# CntrlBoardV3.net
KiCad netlist of a schematic drawn in EAGLE
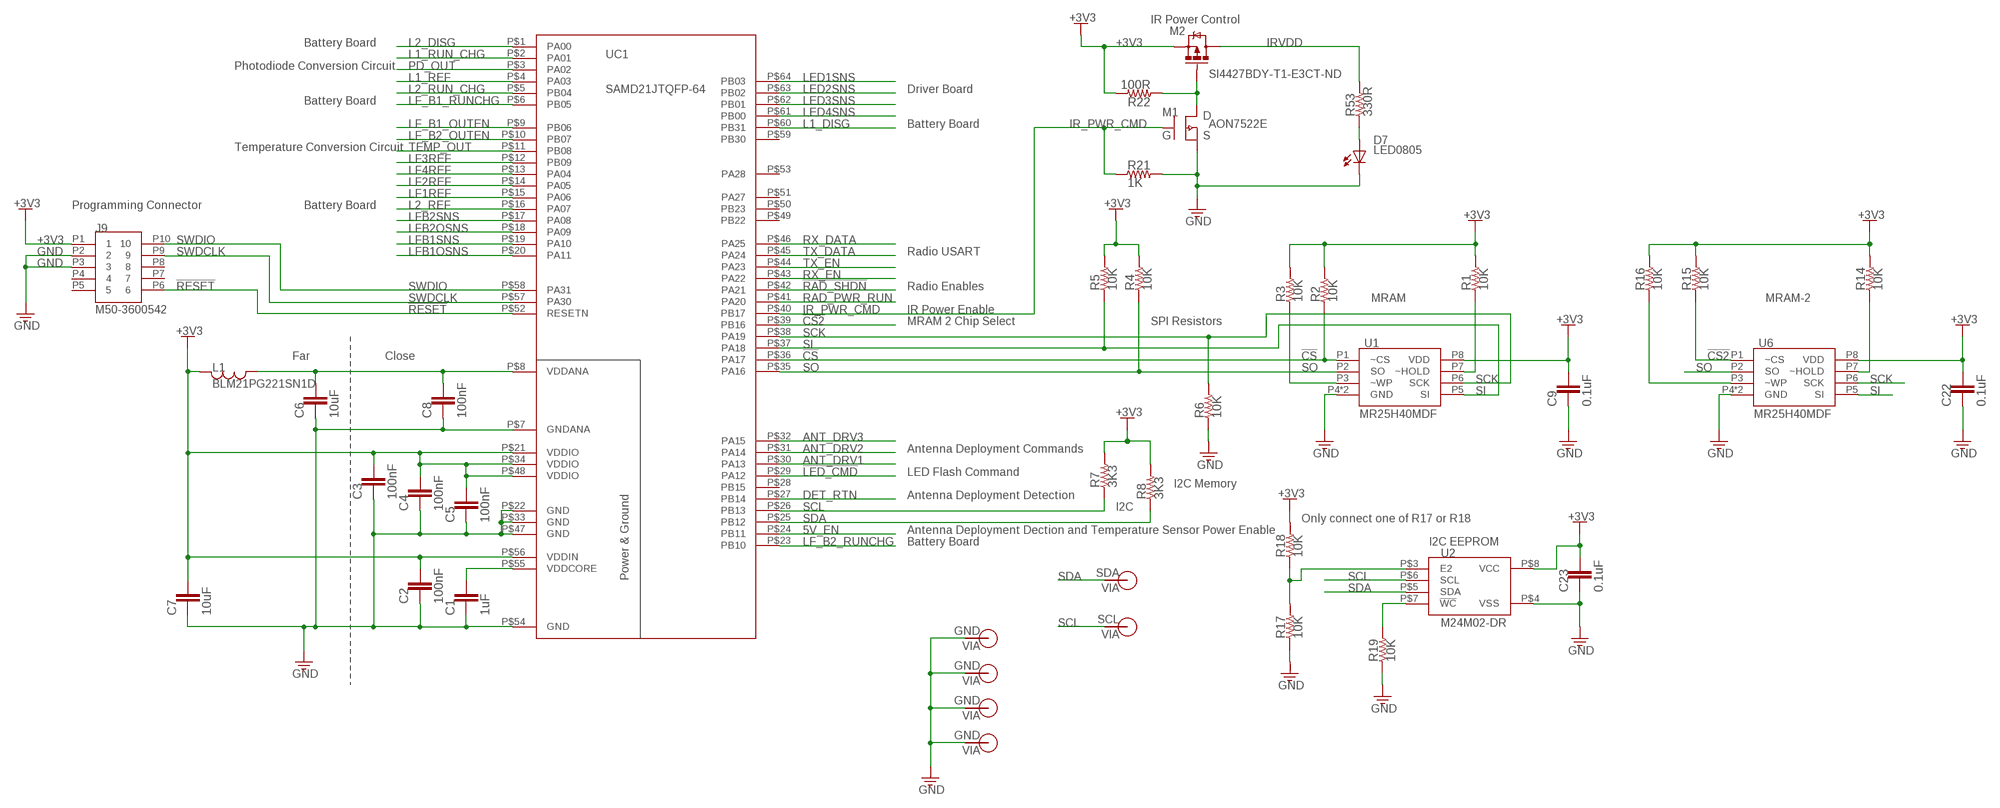
[diagram p0: schematic, sheet 1]
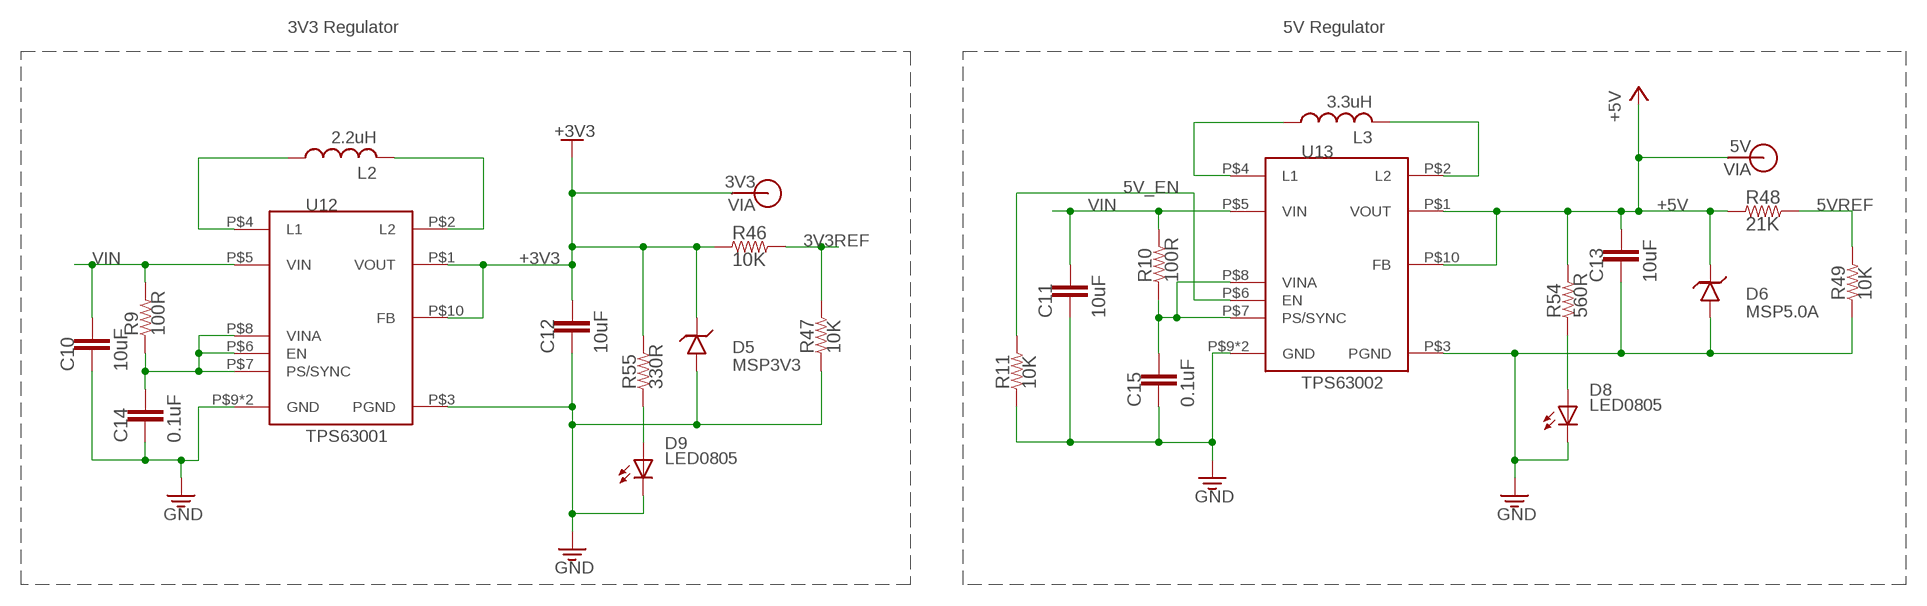
[diagram p1: schematic, sheet 2]
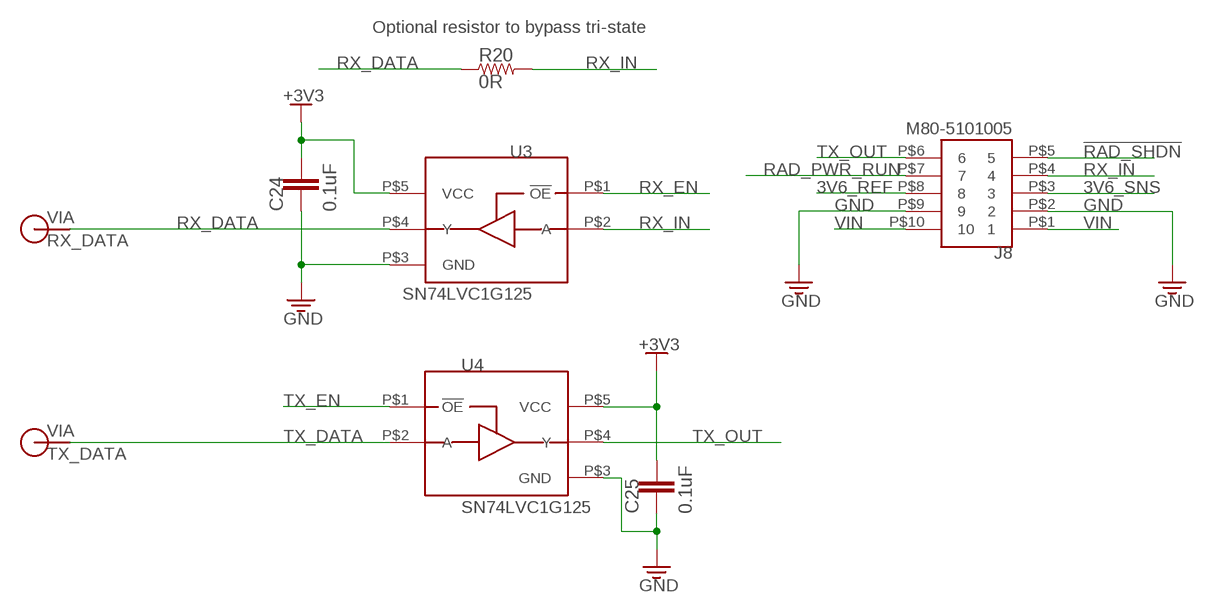
[diagram p2: schematic, sheet 3]
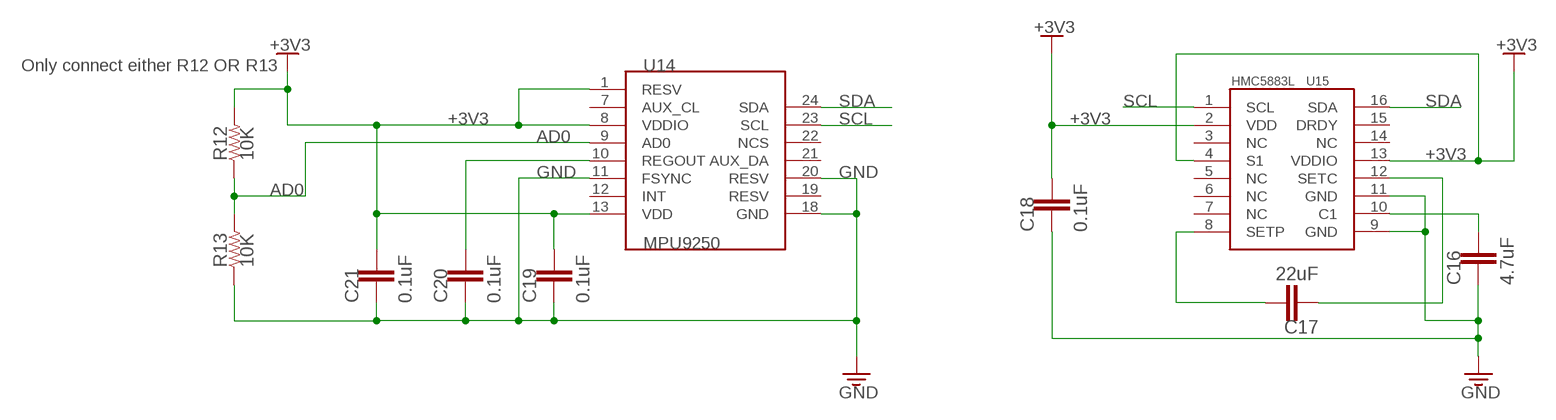
[diagram p3: schematic, sheet 4]
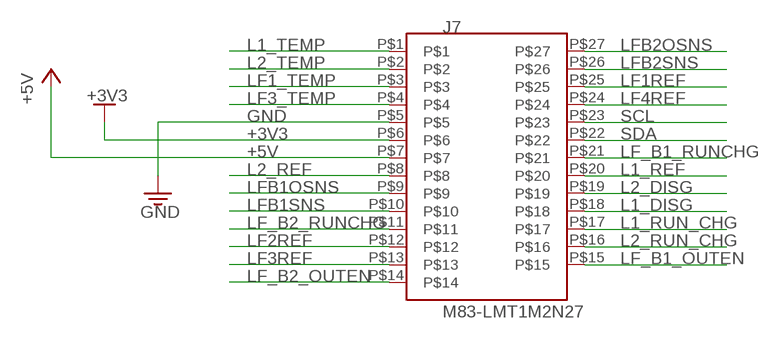
[diagram p4: schematic, sheet 5]
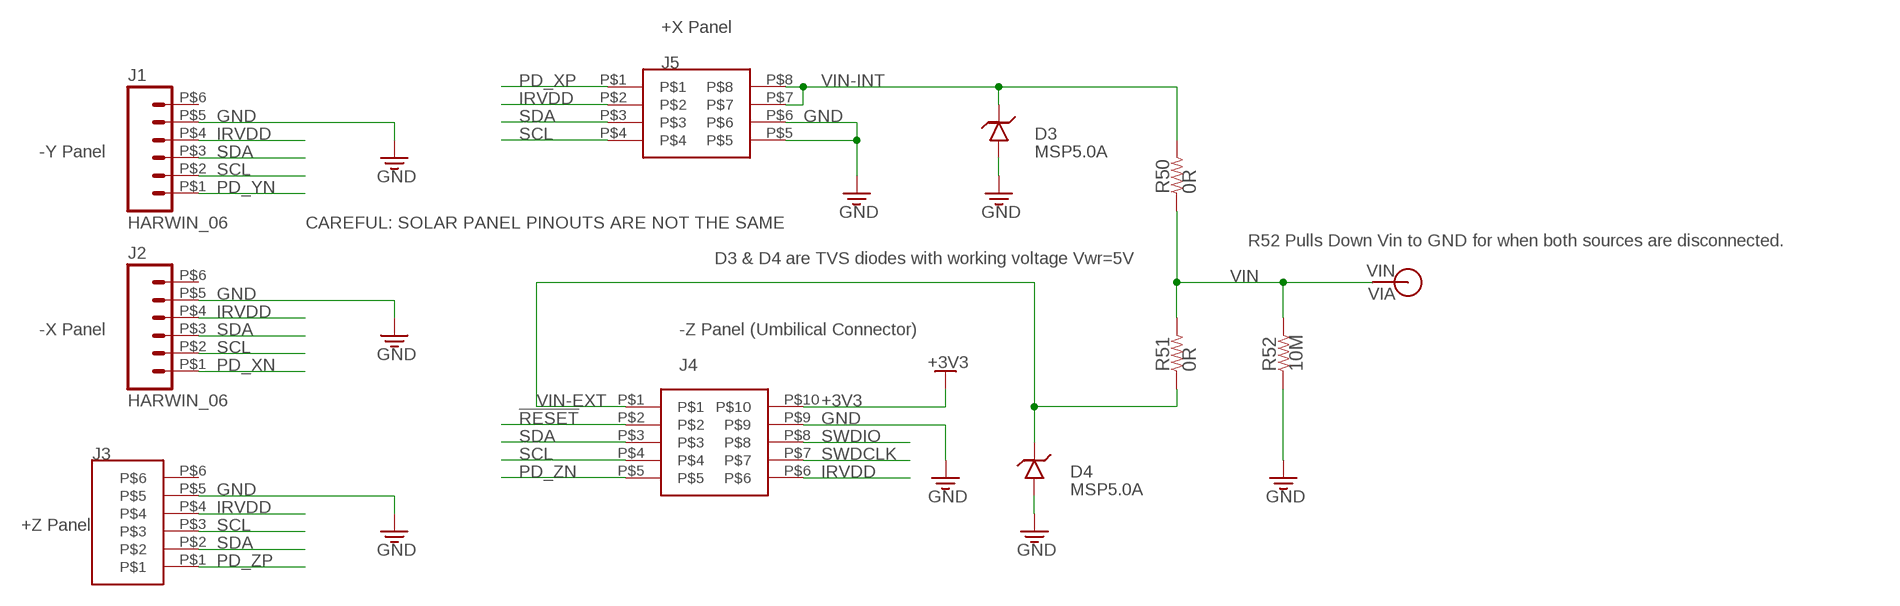
[diagram p5: schematic, sheet 6]
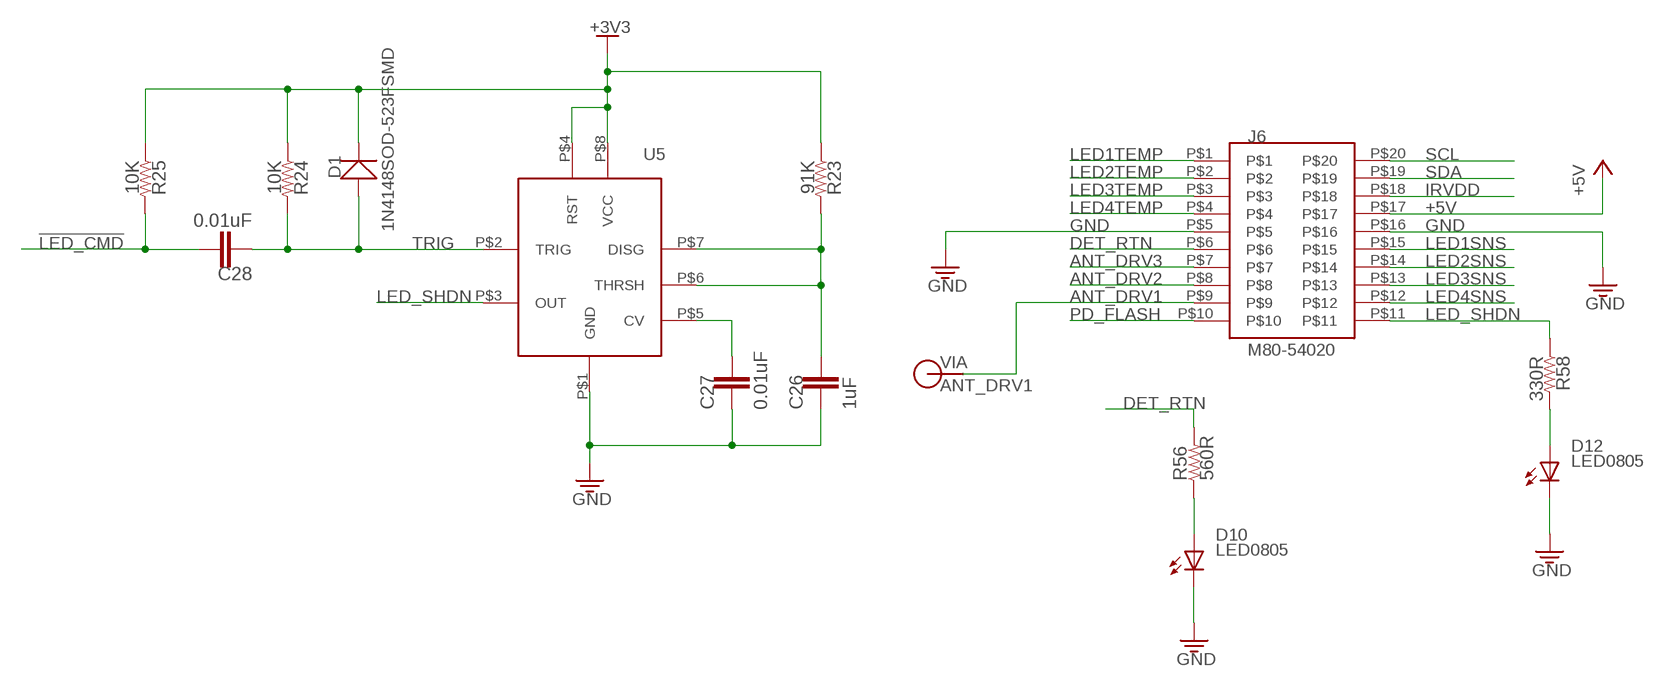
[diagram p6: schematic, sheet 7]
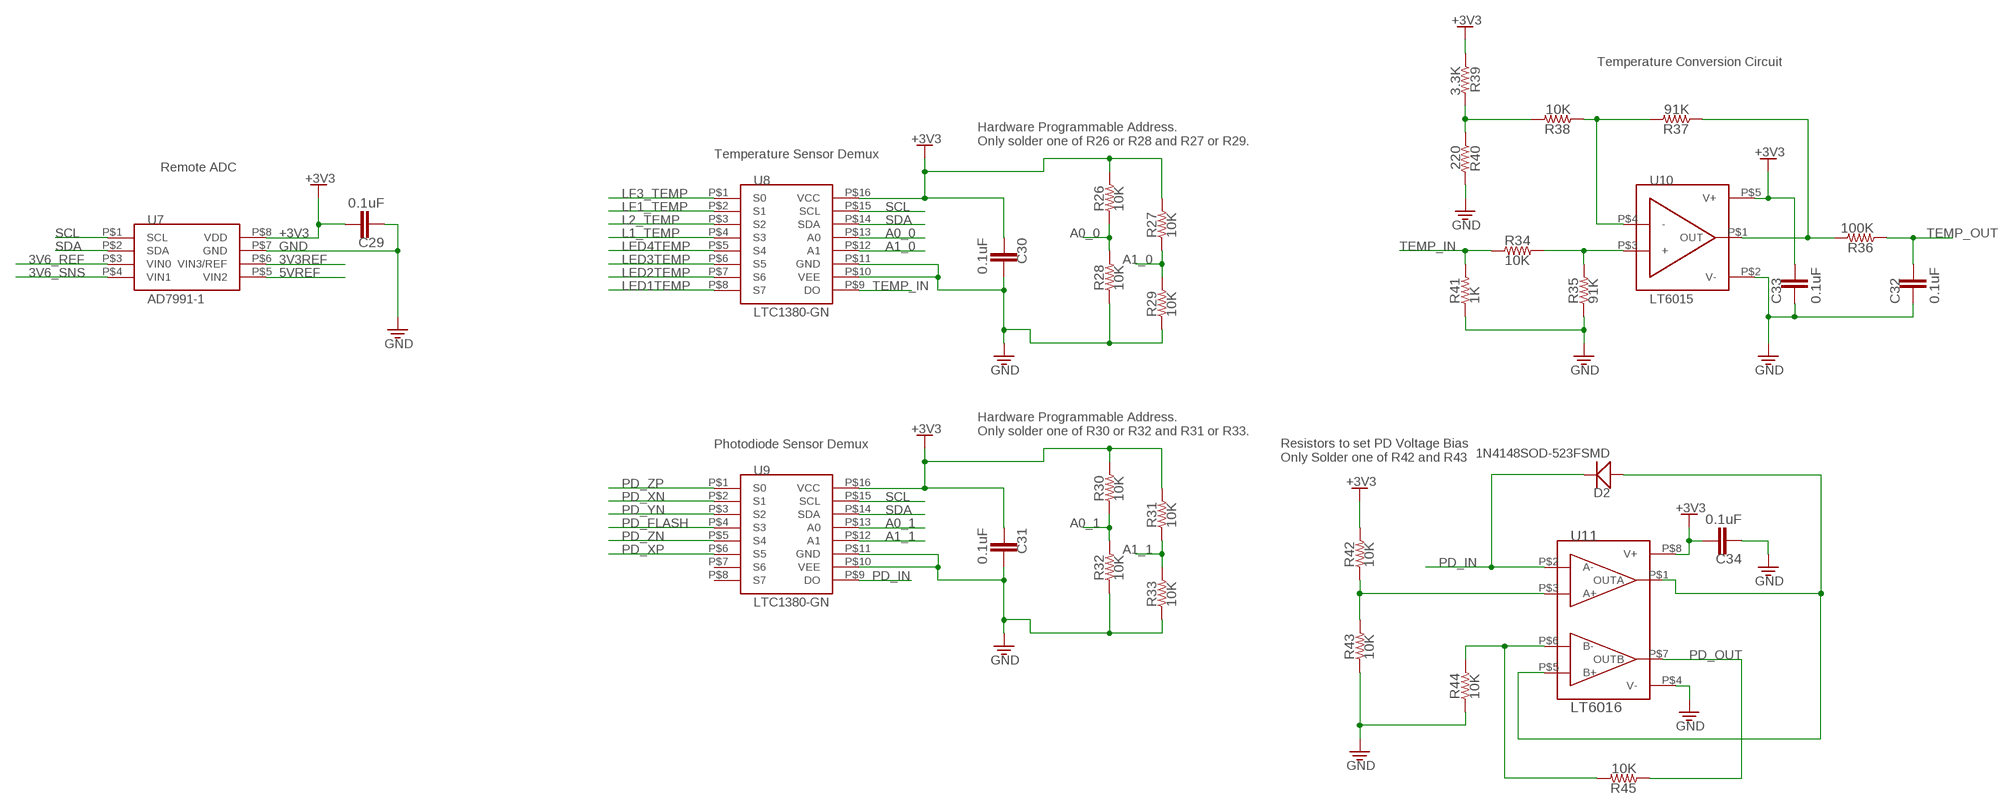
[diagram p7: schematic, sheet 8]

(export (version "E")
  (design (tool "Eeschema 10.0.6"))
  (components
    (comp (ref "C26")
      (value "1uF")
      (footprint "eagle-import:0805")
      (libsource (lib "eagle-import") (part "CAP0805"))
    )
    (comp (ref "C27")
      (value "0.01uF")
      (footprint "eagle-import:0805")
      (libsource (lib "eagle-import") (part "CAP0805"))
    )
    (comp (ref "C28")
      (value "0.01uF")
      (footprint "eagle-import:0805")
      (libsource (lib "eagle-import") (part "CAP0805"))
    )
    (comp (ref "D1")
      (value "1N4148SOD-523FSMD")
      (footprint "eagle-import:SOD-523F")
      (libsource (lib "eagle-import") (part "1N4148SMDSOD-523F"))
    )
    (comp (ref "D10")
      (value "LED0805")
      (footprint "eagle-import:0805-D")
      (libsource (lib "eagle-import") (part "LED0805"))
    )
    (comp (ref "D12")
      (value "LED0805")
      (footprint "eagle-import:0805-D")
      (libsource (lib "eagle-import") (part "LED0805"))
    )
    (comp (ref "J6")
      (value "M80-54020")
      (footprint "eagle-import:M80-54020")
      (libsource (lib "eagle-import") (part "M80-54020"))
    )
    (comp (ref "R23")
      (value "91K")
      (footprint "eagle-import:0805")
      (libsource (lib "eagle-import") (part "RES0805"))
    )
    (comp (ref "R24")
      (value "10K")
      (footprint "eagle-import:0805")
      (libsource (lib "eagle-import") (part "RES0805"))
    )
    (comp (ref "R25")
      (value "10K")
      (footprint "eagle-import:0805")
      (libsource (lib "eagle-import") (part "RES0805"))
    )
    (comp (ref "R56")
      (value "560R")
      (footprint "eagle-import:0805")
      (libsource (lib "eagle-import") (part "RES0805"))
    )
    (comp (ref "R58")
      (value "330R")
      (footprint "eagle-import:0805")
      (libsource (lib "eagle-import") (part "RES0805"))
    )
    (comp (ref "U5")
      (value "TLC555")
      (footprint "eagle-import:SO-8")
      (libsource (lib "eagle-import") (part "TLC555"))
    )
    (comp (ref "V6")
      (value "ANT_DRV1")
      (footprint "eagle-import:VIA-60MIL-SQ")
      (libsource (lib "eagle-import") (part "VIA60MIL-SQ"))
    )
    (comp (ref "C16")
      (value "4.7uF")
      (footprint "eagle-import:0805")
      (libsource (lib "eagle-import") (part "CAP0805"))
    )
    (comp (ref "C17")
      (value "22uF")
      (footprint "eagle-import:0805")
      (libsource (lib "eagle-import") (part "CAP0805"))
    )
    (comp (ref "C18")
      (value "0.1uF")
      (footprint "eagle-import:0805")
      (libsource (lib "eagle-import") (part "CAP0805"))
    )
    (comp (ref "C19")
      (value "0.1uF")
      (footprint "eagle-import:0805")
      (libsource (lib "eagle-import") (part "CAP0805"))
    )
    (comp (ref "C20")
      (value "0.1uF")
      (footprint "eagle-import:0805")
      (libsource (lib "eagle-import") (part "CAP0805"))
    )
    (comp (ref "C21")
      (value "0.1uF")
      (footprint "eagle-import:0805")
      (libsource (lib "eagle-import") (part "CAP0805"))
    )
    (comp (ref "R12")
      (value "10K")
      (footprint "eagle-import:0805")
      (libsource (lib "eagle-import") (part "RES0805"))
    )
    (comp (ref "R13")
      (value "10K")
      (footprint "eagle-import:0805")
      (libsource (lib "eagle-import") (part "RES0805"))
    )
    (comp (ref "U14")
      (value "MPU9250")
      (footprint "eagle-import:QFN-24-3X3")
      (libsource (lib "eagle-import") (part "MPU9250"))
    )
    (comp (ref "U15")
      (value "HMC5883L")
      (footprint "eagle-import:HMC5883L")
      (libsource (lib "eagle-import") (part "HMC5883L"))
    )
    (comp (ref "C10")
      (value "10uF")
      (footprint "eagle-import:0805")
      (libsource (lib "eagle-import") (part "CAP0805"))
    )
    (comp (ref "C11")
      (value "10uF")
      (footprint "eagle-import:0805")
      (libsource (lib "eagle-import") (part "CAP0805"))
    )
    (comp (ref "C12")
      (value "10uF")
      (footprint "eagle-import:0805")
      (libsource (lib "eagle-import") (part "CAP0805"))
    )
    (comp (ref "C13")
      (value "10uF")
      (footprint "eagle-import:0805")
      (libsource (lib "eagle-import") (part "CAP0805"))
    )
    (comp (ref "C14")
      (value "0.1uF")
      (footprint "eagle-import:0805")
      (libsource (lib "eagle-import") (part "CAP0805"))
    )
    (comp (ref "C15")
      (value "0.1uF")
      (footprint "eagle-import:0805")
      (libsource (lib "eagle-import") (part "CAP0805"))
    )
    (comp (ref "D5")
      (value "MSP3V3")
      (footprint "eagle-import:MICROSMP")
      (libsource (lib "eagle-import") (part "TVSMSP"))
    )
    (comp (ref "D6")
      (value "MSP5.0A")
      (footprint "eagle-import:MICROSMP")
      (libsource (lib "eagle-import") (part "TVSMSP"))
    )
    (comp (ref "D8")
      (value "LED0805")
      (footprint "eagle-import:0805-D")
      (libsource (lib "eagle-import") (part "LED0805"))
    )
    (comp (ref "D9")
      (value "LED0805")
      (footprint "eagle-import:0805-D")
      (libsource (lib "eagle-import") (part "LED0805"))
    )
    (comp (ref "L2")
      (value "2.2uH")
      (footprint "eagle-import:L3225M")
      (libsource (lib "eagle-import") (part "L-USL3225M"))
    )
    (comp (ref "L3")
      (value "3.3uH")
      (footprint "eagle-import:L3225M")
      (libsource (lib "eagle-import") (part "L-USL3225M"))
    )
    (comp (ref "R9")
      (value "100R")
      (footprint "eagle-import:0805")
      (libsource (lib "eagle-import") (part "RES0805"))
    )
    (comp (ref "R10")
      (value "100R")
      (footprint "eagle-import:0805")
      (libsource (lib "eagle-import") (part "RES0805"))
    )
    (comp (ref "R11")
      (value "10K")
      (footprint "eagle-import:0805")
      (libsource (lib "eagle-import") (part "RES0805"))
    )
    (comp (ref "R46")
      (value "10K")
      (footprint "eagle-import:0805")
      (libsource (lib "eagle-import") (part "RES0805"))
    )
    (comp (ref "R47")
      (value "10K")
      (footprint "eagle-import:0805")
      (libsource (lib "eagle-import") (part "RES0805"))
    )
    (comp (ref "R48")
      (value "21K")
      (footprint "eagle-import:0805")
      (libsource (lib "eagle-import") (part "RES0805"))
    )
    (comp (ref "R49")
      (value "10K")
      (footprint "eagle-import:0805")
      (libsource (lib "eagle-import") (part "RES0805"))
    )
    (comp (ref "R54")
      (value "560R")
      (footprint "eagle-import:0805")
      (libsource (lib "eagle-import") (part "RES0805"))
    )
    (comp (ref "R55")
      (value "330R")
      (footprint "eagle-import:0805")
      (libsource (lib "eagle-import") (part "RES0805"))
    )
    (comp (ref "U12")
      (value "TPS63001")
      (footprint "eagle-import:QFN10_POWERPAD")
      (libsource (lib "eagle-import") (part "TPS6300X"))
    )
    (comp (ref "U13")
      (value "TPS63002")
      (footprint "eagle-import:QFN10_POWERPAD")
      (libsource (lib "eagle-import") (part "TPS6300X"))
    )
    (comp (ref "V13")
      (value "3V3")
      (footprint "eagle-import:VIA-60MIL-SQ")
      (libsource (lib "eagle-import") (part "VIA60MIL-SQ"))
    )
    (comp (ref "V14")
      (value "5V")
      (footprint "eagle-import:VIA-60MIL-SQ")
      (libsource (lib "eagle-import") (part "VIA60MIL-SQ"))
    )
    (comp (ref "C29")
      (value "0.1uF")
      (footprint "eagle-import:0805")
      (libsource (lib "eagle-import") (part "CAP0805"))
    )
    (comp (ref "C30")
      (value "0.1uF")
      (footprint "eagle-import:0805")
      (libsource (lib "eagle-import") (part "CAP0805"))
    )
    (comp (ref "C31")
      (value "0.1uF")
      (footprint "eagle-import:0805")
      (libsource (lib "eagle-import") (part "CAP0805"))
    )
    (comp (ref "C32")
      (value "0.1uF")
      (footprint "eagle-import:0805")
      (libsource (lib "eagle-import") (part "CAP0805"))
    )
    (comp (ref "C33")
      (value "0.1uF")
      (footprint "eagle-import:0805")
      (libsource (lib "eagle-import") (part "CAP0805"))
    )
    (comp (ref "C34")
      (value "0.1uF")
      (footprint "eagle-import:0805")
      (libsource (lib "eagle-import") (part "CAP0805"))
    )
    (comp (ref "D2")
      (value "1N4148SOD-523FSMD")
      (footprint "eagle-import:SOD-523F")
      (libsource (lib "eagle-import") (part "1N4148SMDSOD-523F"))
    )
    (comp (ref "R26")
      (value "10K")
      (footprint "eagle-import:0805")
      (libsource (lib "eagle-import") (part "RES0805"))
    )
    (comp (ref "R27")
      (value "10K")
      (footprint "eagle-import:0805")
      (libsource (lib "eagle-import") (part "RES0805"))
    )
    (comp (ref "R28")
      (value "10K")
      (footprint "eagle-import:0805")
      (libsource (lib "eagle-import") (part "RES0805"))
    )
    (comp (ref "R29")
      (value "10K")
      (footprint "eagle-import:0805")
      (libsource (lib "eagle-import") (part "RES0805"))
    )
    (comp (ref "R30")
      (value "10K")
      (footprint "eagle-import:0805")
      (libsource (lib "eagle-import") (part "RES0805"))
    )
    (comp (ref "R31")
      (value "10K")
      (footprint "eagle-import:0805")
      (libsource (lib "eagle-import") (part "RES0805"))
    )
    (comp (ref "R32")
      (value "10K")
      (footprint "eagle-import:0805")
      (libsource (lib "eagle-import") (part "RES0805"))
    )
    (comp (ref "R33")
      (value "10K")
      (footprint "eagle-import:0805")
      (libsource (lib "eagle-import") (part "RES0805"))
    )
    (comp (ref "R34")
      (value "10K")
      (footprint "eagle-import:0805")
      (libsource (lib "eagle-import") (part "RES0805"))
    )
    (comp (ref "R35")
      (value "91K")
      (footprint "eagle-import:0805")
      (libsource (lib "eagle-import") (part "RES0805"))
    )
    (comp (ref "R36")
      (value "100K")
      (footprint "eagle-import:0805")
      (libsource (lib "eagle-import") (part "RES0805"))
    )
    (comp (ref "R37")
      (value "91K")
      (footprint "eagle-import:0805")
      (libsource (lib "eagle-import") (part "RES0805"))
    )
    (comp (ref "R38")
      (value "10K")
      (footprint "eagle-import:0805")
      (libsource (lib "eagle-import") (part "RES0805"))
    )
    (comp (ref "R39")
      (value "3.3K")
      (footprint "eagle-import:0805")
      (libsource (lib "eagle-import") (part "RES0805"))
    )
    (comp (ref "R40")
      (value "220")
      (footprint "eagle-import:0805")
      (libsource (lib "eagle-import") (part "RES0805"))
    )
    (comp (ref "R41")
      (value "1K")
      (footprint "eagle-import:0805")
      (libsource (lib "eagle-import") (part "RES0805"))
    )
    (comp (ref "R42")
      (value "10K")
      (footprint "eagle-import:0805")
      (libsource (lib "eagle-import") (part "RES0805"))
    )
    (comp (ref "R43")
      (value "10K")
      (footprint "eagle-import:0805")
      (libsource (lib "eagle-import") (part "RES0805"))
    )
    (comp (ref "R44")
      (value "10K")
      (footprint "eagle-import:0805")
      (libsource (lib "eagle-import") (part "RES0805"))
    )
    (comp (ref "R45")
      (value "10K")
      (footprint "eagle-import:0805")
      (libsource (lib "eagle-import") (part "RES0805"))
    )
    (comp (ref "U7")
      (value "AD7991-1")
      (footprint "eagle-import:SOT-23-8")
      (libsource (lib "eagle-import") (part "AD7991-1"))
    )
    (comp (ref "U8")
      (value "LTC1380-GN")
      (footprint "eagle-import:SSOP-16-NARROW")
      (libsource (lib "eagle-import") (part "LTC1380-GN"))
    )
    (comp (ref "U9")
      (value "LTC1380-GN")
      (footprint "eagle-import:SSOP-16-NARROW")
      (libsource (lib "eagle-import") (part "LTC1380-GN"))
    )
    (comp (ref "U10")
      (value "LT6015")
      (footprint "eagle-import:TSOT23-5")
      (libsource (lib "eagle-import") (part "LT6015"))
    )
    (comp (ref "U11")
      (value "LT6016")
      (footprint "eagle-import:MSOP-8")
      (libsource (lib "eagle-import") (part "LT6016"))
    )
    (comp (ref "C1")
      (value "1uF")
      (footprint "eagle-import:0805")
      (libsource (lib "eagle-import") (part "CAP0805"))
    )
    (comp (ref "C2")
      (value "100nF")
      (footprint "eagle-import:0805")
      (libsource (lib "eagle-import") (part "CAP0805"))
    )
    (comp (ref "C3")
      (value "100nF")
      (footprint "eagle-import:0805")
      (libsource (lib "eagle-import") (part "CAP0805"))
    )
    (comp (ref "C4")
      (value "100nF")
      (footprint "eagle-import:0805")
      (libsource (lib "eagle-import") (part "CAP0805"))
    )
    (comp (ref "C5")
      (value "100nF")
      (footprint "eagle-import:0805")
      (libsource (lib "eagle-import") (part "CAP0805"))
    )
    (comp (ref "C6")
      (value "10uF")
      (footprint "eagle-import:0805")
      (libsource (lib "eagle-import") (part "CAP0805"))
    )
    (comp (ref "C7")
      (value "10uF")
      (footprint "eagle-import:0805")
      (libsource (lib "eagle-import") (part "CAP0805"))
    )
    (comp (ref "C8")
      (value "100nF")
      (footprint "eagle-import:0805")
      (libsource (lib "eagle-import") (part "CAP0805"))
    )
    (comp (ref "C9")
      (value "0.1uF")
      (footprint "eagle-import:0805")
      (libsource (lib "eagle-import") (part "CAP0805"))
    )
    (comp (ref "C22")
      (value "0.1uF")
      (footprint "eagle-import:0805")
      (libsource (lib "eagle-import") (part "CAP0805"))
    )
    (comp (ref "C23")
      (value "0.1uF")
      (footprint "eagle-import:0805")
      (libsource (lib "eagle-import") (part "CAP0805"))
    )
    (comp (ref "D7")
      (value "LED0805")
      (footprint "eagle-import:0805-D")
      (libsource (lib "eagle-import") (part "LED0805"))
    )
    (comp (ref "J9")
      (value "M50-3600542")
      (footprint "eagle-import:10PINMALE")
      (libsource (lib "eagle-import") (part "10PINMALE"))
    )
    (comp (ref "L1")
      (value "BLM21PG221SN1D")
      (footprint "eagle-import:0805")
      (libsource (lib "eagle-import") (part "FERRITE"))
    )
    (comp (ref "M1")
      (value "AON7522E")
      (footprint "eagle-import:DFN-3X3-8")
      (libsource (lib "eagle-import") (part "AON7522E"))
    )
    (comp (ref "M2")
      (value "SI4427BDY-T1-E3CT-ND")
      (footprint "eagle-import:SO08")
      (libsource (lib "eagle-import") (part "POWERPMOS"))
    )
    (comp (ref "R1")
      (value "10K")
      (footprint "eagle-import:0805")
      (libsource (lib "eagle-import") (part "RES0805"))
    )
    (comp (ref "R2")
      (value "10K")
      (footprint "eagle-import:0805")
      (libsource (lib "eagle-import") (part "RES0805"))
    )
    (comp (ref "R3")
      (value "10K")
      (footprint "eagle-import:0805")
      (libsource (lib "eagle-import") (part "RES0805"))
    )
    (comp (ref "R4")
      (value "10K")
      (footprint "eagle-import:0805")
      (libsource (lib "eagle-import") (part "RES0805"))
    )
    (comp (ref "R5")
      (value "10K")
      (footprint "eagle-import:0805")
      (libsource (lib "eagle-import") (part "RES0805"))
    )
    (comp (ref "R6")
      (value "10K")
      (footprint "eagle-import:0805")
      (libsource (lib "eagle-import") (part "RES0805"))
    )
    (comp (ref "R7")
      (value "3K3")
      (footprint "eagle-import:0805")
      (libsource (lib "eagle-import") (part "RES0805"))
    )
    (comp (ref "R8")
      (value "3K3")
      (footprint "eagle-import:0805")
      (libsource (lib "eagle-import") (part "RES0805"))
    )
    (comp (ref "R14")
      (value "10K")
      (footprint "eagle-import:0805")
      (libsource (lib "eagle-import") (part "RES0805"))
    )
    (comp (ref "R15")
      (value "10K")
      (footprint "eagle-import:0805")
      (libsource (lib "eagle-import") (part "RES0805"))
    )
    (comp (ref "R16")
      (value "10K")
      (footprint "eagle-import:0805")
      (libsource (lib "eagle-import") (part "RES0805"))
    )
    (comp (ref "R17")
      (value "10K")
      (footprint "eagle-import:0805")
      (libsource (lib "eagle-import") (part "RES0805"))
    )
    (comp (ref "R18")
      (value "10K")
      (footprint "eagle-import:0805")
      (libsource (lib "eagle-import") (part "RES0805"))
    )
    (comp (ref "R19")
      (value "10K")
      (footprint "eagle-import:0805")
      (libsource (lib "eagle-import") (part "RES0805"))
    )
    (comp (ref "R21")
      (value "1K")
      (footprint "eagle-import:0805")
      (libsource (lib "eagle-import") (part "RES0805"))
    )
    (comp (ref "R22")
      (value "100R")
      (footprint "eagle-import:0805")
      (libsource (lib "eagle-import") (part "RES0805"))
    )
    (comp (ref "R53")
      (value "330R")
      (footprint "eagle-import:0805")
      (libsource (lib "eagle-import") (part "RES0805"))
    )
    (comp (ref "U1")
      (value "MR25H40MDF")
      (footprint "eagle-import:8PXMO-229")
      (libsource (lib "eagle-import") (part "MR2XHXX"))
    )
    (comp (ref "U2")
      (value "M24M02-DR")
      (footprint "eagle-import:SO-8")
      (libsource (lib "eagle-import") (part "M24M02-DR"))
    )
    (comp (ref "U6")
      (value "MR25H40MDF")
      (footprint "eagle-import:8PXMO-229")
      (libsource (lib "eagle-import") (part "MR2XHXX"))
    )
    (comp (ref "UC1")
      (value "SAMD21JTQFP-64")
      (footprint "eagle-import:TQFP-64")
      (libsource (lib "eagle-import") (part "SAMD21JTQFP-64"))
    )
    (comp (ref "V4")
      (value "SDA")
      (footprint "eagle-import:VIA-60MIL-SQ")
      (libsource (lib "eagle-import") (part "VIA60MIL-SQ"))
    )
    (comp (ref "V5")
      (value "SCL")
      (footprint "eagle-import:VIA-60MIL-SQ")
      (libsource (lib "eagle-import") (part "VIA60MIL-SQ"))
    )
    (comp (ref "V9")
      (value "GND")
      (footprint "eagle-import:VIA-60MIL-SQ")
      (libsource (lib "eagle-import") (part "VIA60MIL-SQ"))
    )
    (comp (ref "V10")
      (value "GND")
      (footprint "eagle-import:VIA-60MIL-SQ")
      (libsource (lib "eagle-import") (part "VIA60MIL-SQ"))
    )
    (comp (ref "V11")
      (value "GND")
      (footprint "eagle-import:VIA-60MIL-SQ")
      (libsource (lib "eagle-import") (part "VIA60MIL-SQ"))
    )
    (comp (ref "V12")
      (value "GND")
      (footprint "eagle-import:VIA-60MIL-SQ")
      (libsource (lib "eagle-import") (part "VIA60MIL-SQ"))
    )
    (comp (ref "D3")
      (value "MSP5.0A")
      (footprint "eagle-import:MICROSMP")
      (libsource (lib "eagle-import") (part "TVSMSP"))
    )
    (comp (ref "D4")
      (value "MSP5.0A")
      (footprint "eagle-import:MICROSMP")
      (libsource (lib "eagle-import") (part "TVSMSP"))
    )
    (comp (ref "J1")
      (value "HARWIN_06")
      (footprint "eagle-import:HARWIN_DATAMATE_6")
      (libsource (lib "eagle-import") (part "HARWIN_06"))
    )
    (comp (ref "J2")
      (value "HARWIN_06")
      (footprint "eagle-import:HARWIN_DATAMATE_6")
      (libsource (lib "eagle-import") (part "HARWIN_06"))
    )
    (comp (ref "J3")
      (value "M80-54006")
      (footprint "eagle-import:M80-54006")
      (libsource (lib "eagle-import") (part "M80-54006"))
    )
    (comp (ref "J4")
      (value "M80-54010")
      (footprint "eagle-import:M80-54010")
      (libsource (lib "eagle-import") (part "M80-54010"))
    )
    (comp (ref "J5")
      (value "M80-54008")
      (footprint "eagle-import:M80-54008")
      (libsource (lib "eagle-import") (part "M80-54008"))
    )
    (comp (ref "R50")
      (value "0R")
      (footprint "eagle-import:1210")
      (libsource (lib "eagle-import") (part "RES1210"))
    )
    (comp (ref "R51")
      (value "0R")
      (footprint "eagle-import:1210")
      (libsource (lib "eagle-import") (part "RES1210"))
    )
    (comp (ref "R52")
      (value "10M")
      (footprint "eagle-import:0805")
      (libsource (lib "eagle-import") (part "RES0805"))
    )
    (comp (ref "V3")
      (value "VIN")
      (footprint "eagle-import:VIA-60MIL-SQ")
      (libsource (lib "eagle-import") (part "VIA60MIL-SQ"))
    )
    (comp (ref "C24")
      (value "0.1uF")
      (footprint "eagle-import:0805")
      (libsource (lib "eagle-import") (part "CAP0805"))
    )
    (comp (ref "C25")
      (value "0.1uF")
      (footprint "eagle-import:0805")
      (libsource (lib "eagle-import") (part "CAP0805"))
    )
    (comp (ref "J8")
      (value "M80-5101005")
      (footprint "eagle-import:M80-510")
      (libsource (lib "eagle-import") (part "M80-5101005"))
    )
    (comp (ref "R20")
      (value "0R")
      (footprint "eagle-import:0805")
      (libsource (lib "eagle-import") (part "RES0805"))
    )
    (comp (ref "U3")
      (value "SN74LVC1G125")
      (footprint "eagle-import:TSOT23-5")
      (libsource (lib "eagle-import") (part "SN74LVC1G125"))
    )
    (comp (ref "U4")
      (value "SN74LVC1G125")
      (footprint "eagle-import:TSOT23-5")
      (libsource (lib "eagle-import") (part "SN74LVC1G125"))
    )
    (comp (ref "V1")
      (value "RX_DATA")
      (footprint "eagle-import:VIA-60MIL-SQ")
      (libsource (lib "eagle-import") (part "VIA60MIL-SQ"))
    )
    (comp (ref "V2")
      (value "TX_DATA")
      (footprint "eagle-import:VIA-60MIL-SQ")
      (libsource (lib "eagle-import") (part "VIA60MIL-SQ"))
    )
    (comp (ref "J7")
      (value "M83-LMT1M2N27")
      (footprint "eagle-import:M83-LMT1M2N27")
      (libsource (lib "eagle-import") (part "M83-LMT1M2N27"))
    )
  )
  (nets
    (net (code "1") (name "+3V3") (class "Default")
      (node (ref "C12") (pin "1") (pinfunction "P$1_1") (pintype "passive"))
      (node (ref "C18") (pin "1") (pinfunction "P$1_1") (pintype "passive"))
      (node (ref "C19") (pin "1") (pinfunction "P$1_1") (pintype "passive"))
      (node (ref "C2") (pin "1") (pinfunction "P$1_1") (pintype "passive"))
      (node (ref "C21") (pin "1") (pinfunction "P$1_1") (pintype "passive"))
      (node (ref "C22") (pin "1") (pinfunction "P$1_1") (pintype "passive"))
      (node (ref "C23") (pin "1") (pinfunction "P$1_1") (pintype "passive"))
      (node (ref "C24") (pin "1") (pinfunction "P$1_1") (pintype "passive"))
      (node (ref "C25") (pin "1") (pinfunction "P$1_1") (pintype "passive"))
      (node (ref "C29") (pin "1") (pinfunction "P$1_1") (pintype "passive"))
      (node (ref "C3") (pin "1") (pinfunction "P$1_1") (pintype "passive"))
      (node (ref "C30") (pin "2") (pinfunction "P$2_2") (pintype "passive"))
      (node (ref "C31") (pin "2") (pinfunction "P$2_2") (pintype "passive"))
      (node (ref "C33") (pin "1") (pinfunction "P$1_1") (pintype "passive"))
      (node (ref "C34") (pin "1") (pinfunction "P$1_1") (pintype "passive"))
      (node (ref "C4") (pin "1") (pinfunction "P$1_1") (pintype "passive"))
      (node (ref "C5") (pin "1") (pinfunction "P$1_1") (pintype "passive"))
      (node (ref "C7") (pin "1") (pinfunction "P$1_1") (pintype "passive"))
      (node (ref "C9") (pin "1") (pinfunction "P$1_1") (pintype "passive"))
      (node (ref "D1") (pin "C") (pinfunction "C_C") (pintype "bidirectional"))
      (node (ref "D5") (pin "C") (pinfunction "C_C") (pintype "bidirectional"))
      (node (ref "J4") (pin "P$10") (pinfunction "P$10_P$10") (pintype "bidirectional"))
      (node (ref "J7") (pin "P$6") (pinfunction "P$6_P$6") (pintype "bidirectional"))
      (node (ref "J9") (pin "P1") (pinfunction "1_P1") (pintype "bidirectional"))
      (node (ref "L1") (pin "1") (pinfunction "P$1_1") (pintype "passive"))
      (node (ref "M2") (pin "1") (pinfunction "S_1") (pintype "passive"))
      (node (ref "M2") (pin "2") (pinfunction "S_2") (pintype "passive"))
      (node (ref "M2") (pin "3") (pinfunction "S_3") (pintype "passive"))
      (node (ref "R1") (pin "2") (pinfunction "2_2") (pintype "passive"))
      (node (ref "R12") (pin "2") (pinfunction "2_2") (pintype "passive"))
      (node (ref "R14") (pin "2") (pinfunction "2_2") (pintype "passive"))
      (node (ref "R15") (pin "2") (pinfunction "2_2") (pintype "passive"))
      (node (ref "R16") (pin "2") (pinfunction "2_2") (pintype "passive"))
      (node (ref "R18") (pin "2") (pinfunction "2_2") (pintype "passive"))
      (node (ref "R2") (pin "2") (pinfunction "2_2") (pintype "passive"))
      (node (ref "R22") (pin "2") (pinfunction "2_2") (pintype "passive"))
      (node (ref "R23") (pin "1") (pinfunction "1_1") (pintype "passive"))
      (node (ref "R24") (pin "1") (pinfunction "1_1") (pintype "passive"))
      (node (ref "R25") (pin "1") (pinfunction "1_1") (pintype "passive"))
      (node (ref "R26") (pin "2") (pinfunction "2_2") (pintype "passive"))
      (node (ref "R27") (pin "2") (pinfunction "2_2") (pintype "passive"))
      (node (ref "R3") (pin "2") (pinfunction "2_2") (pintype "passive"))
      (node (ref "R30") (pin "2") (pinfunction "2_2") (pintype "passive"))
      (node (ref "R31") (pin "2") (pinfunction "2_2") (pintype "passive"))
      (node (ref "R39") (pin "1") (pinfunction "1_1") (pintype "passive"))
      (node (ref "R4") (pin "2") (pinfunction "2_2") (pintype "passive"))
      (node (ref "R42") (pin "2") (pinfunction "2_2") (pintype "passive"))
      (node (ref "R46") (pin "1") (pinfunction "1_1") (pintype "passive"))
      (node (ref "R5") (pin "2") (pinfunction "2_2") (pintype "passive"))
      (node (ref "R55") (pin "2") (pinfunction "2_2") (pintype "passive"))
      (node (ref "R7") (pin "2") (pinfunction "2_2") (pintype "passive"))
      (node (ref "R8") (pin "2") (pinfunction "2_2") (pintype "passive"))
      (node (ref "U1") (pin "P8") (pinfunction "VDD_P8") (pintype "bidirectional"))
      (node (ref "U10") (pin "P$5") (pinfunction "V+_P$5") (pintype "bidirectional"))
      (node (ref "U11") (pin "P$8") (pinfunction "V+_P$8") (pintype "bidirectional"))
      (node (ref "U12") (pin "P$1") (pinfunction "VOUT_P$1") (pintype "output"))
      (node (ref "U12") (pin "P$10") (pinfunction "FB_P$10") (pintype "input"))
      (node (ref "U14") (pin "1") (pinfunction "RESV_1") (pintype "bidirectional"))
      (node (ref "U14") (pin "13") (pinfunction "VDD_13") (pintype "bidirectional"))
      (node (ref "U14") (pin "8") (pinfunction "VDDIO_8") (pintype "bidirectional"))
      (node (ref "U15") (pin "13") (pinfunction "VDDIO_13") (pintype "bidirectional"))
      (node (ref "U15") (pin "2") (pinfunction "VDD_2") (pintype "bidirectional"))
      (node (ref "U15") (pin "4") (pinfunction "S1_4") (pintype "bidirectional"))
      (node (ref "U2") (pin "P$8") (pinfunction "VCC_P$8") (pintype "bidirectional"))
      (node (ref "U3") (pin "P$5") (pinfunction "VCC_P$5") (pintype "bidirectional"))
      (node (ref "U4") (pin "P$5") (pinfunction "VCC_P$5") (pintype "bidirectional"))
      (node (ref "U5") (pin "P$4") (pinfunction "RST_P$4") (pintype "bidirectional"))
      (node (ref "U5") (pin "P$8") (pinfunction "VCC_P$8") (pintype "bidirectional"))
      (node (ref "U6") (pin "P8") (pinfunction "VDD_P8") (pintype "bidirectional"))
      (node (ref "U7") (pin "P$8") (pinfunction "VDD_P$8") (pintype "bidirectional"))
      (node (ref "U8") (pin "P$16") (pinfunction "VCC_P$16") (pintype "bidirectional"))
      (node (ref "U9") (pin "P$16") (pinfunction "VCC_P$16") (pintype "bidirectional"))
      (node (ref "UC1") (pin "P$21") (pinfunction "VDDIO_P$21") (pintype "power_in"))
      (node (ref "UC1") (pin "P$34") (pinfunction "VDDIO_P$34") (pintype "power_in"))
      (node (ref "UC1") (pin "P$48") (pinfunction "VDDIO_P$48") (pintype "power_in"))
      (node (ref "UC1") (pin "P$56") (pinfunction "VDDIN_P$56") (pintype "power_in"))
      (node (ref "V13") (pin "P$1") (pinfunction "P$1_P$1") (pintype "bidirectional"))
    )
    (net (code "2") (name "+5V") (class "Default")
      (node (ref "C13") (pin "1") (pinfunction "P$1_1") (pintype "passive"))
      (node (ref "D6") (pin "C") (pinfunction "C_C") (pintype "bidirectional"))
      (node (ref "J6") (pin "P$17") (pinfunction "P$17_P$17") (pintype "bidirectional"))
      (node (ref "J7") (pin "P$7") (pinfunction "P$7_P$7") (pintype "bidirectional"))
      (node (ref "R48") (pin "1") (pinfunction "1_1") (pintype "passive"))
      (node (ref "R54") (pin "2") (pinfunction "2_2") (pintype "passive"))
      (node (ref "U13") (pin "P$1") (pinfunction "VOUT_P$1") (pintype "output"))
      (node (ref "U13") (pin "P$10") (pinfunction "FB_P$10") (pintype "input"))
      (node (ref "V14") (pin "P$1") (pinfunction "P$1_P$1") (pintype "bidirectional"))
    )
    (net (code "3") (name "3V3REF") (class "Default")
      (node (ref "R46") (pin "2") (pinfunction "2_2") (pintype "passive"))
      (node (ref "R47") (pin "2") (pinfunction "2_2") (pintype "passive"))
      (node (ref "U7") (pin "P$6") (pinfunction "VIN3/REF_P$6") (pintype "bidirectional"))
    )
    (net (code "4") (name "3V6_REF") (class "Default")
      (node (ref "J8") (pin "P$8") (pinfunction "8_P$8") (pintype "bidirectional"))
      (node (ref "U7") (pin "P$3") (pinfunction "VIN0_P$3") (pintype "bidirectional"))
    )
    (net (code "5") (name "3V6_SNS") (class "Default")
      (node (ref "J8") (pin "P$3") (pinfunction "3_P$3") (pintype "bidirectional"))
      (node (ref "U7") (pin "P$4") (pinfunction "VIN1_P$4") (pintype "bidirectional"))
    )
    (net (code "6") (name "5VREF") (class "Default")
      (node (ref "R48") (pin "2") (pinfunction "2_2") (pintype "passive"))
      (node (ref "R49") (pin "2") (pinfunction "2_2") (pintype "passive"))
      (node (ref "U7") (pin "P$5") (pinfunction "VIN2_P$5") (pintype "bidirectional"))
    )
    (net (code "7") (name "5V_EN") (class "Default")
      (node (ref "R11") (pin "2") (pinfunction "2_2") (pintype "passive"))
      (node (ref "U13") (pin "P$6") (pinfunction "EN_P$6") (pintype "input"))
      (node (ref "UC1") (pin "P$24") (pinfunction "PB11_P$24") (pintype "bidirectional"))
    )
    (net (code "8") (name "A0_0") (class "Default")
      (node (ref "R26") (pin "1") (pinfunction "1_1") (pintype "passive"))
      (node (ref "R28") (pin "2") (pinfunction "2_2") (pintype "passive"))
      (node (ref "U8") (pin "P$13") (pinfunction "A0_P$13") (pintype "bidirectional"))
    )
    (net (code "9") (name "A0_1") (class "Default")
      (node (ref "R30") (pin "1") (pinfunction "1_1") (pintype "passive"))
      (node (ref "R32") (pin "2") (pinfunction "2_2") (pintype "passive"))
      (node (ref "U9") (pin "P$13") (pinfunction "A0_P$13") (pintype "bidirectional"))
    )
    (net (code "10") (name "A1_0") (class "Default")
      (node (ref "R27") (pin "1") (pinfunction "1_1") (pintype "passive"))
      (node (ref "R29") (pin "2") (pinfunction "2_2") (pintype "passive"))
      (node (ref "U8") (pin "P$12") (pinfunction "A1_P$12") (pintype "bidirectional"))
    )
    (net (code "11") (name "A1_1") (class "Default")
      (node (ref "R31") (pin "1") (pinfunction "1_1") (pintype "passive"))
      (node (ref "R33") (pin "2") (pinfunction "2_2") (pintype "passive"))
      (node (ref "U9") (pin "P$12") (pinfunction "A1_P$12") (pintype "bidirectional"))
    )
    (net (code "12") (name "AD0") (class "Default")
      (node (ref "R12") (pin "1") (pinfunction "1_1") (pintype "passive"))
      (node (ref "R13") (pin "2") (pinfunction "2_2") (pintype "passive"))
      (node (ref "U14") (pin "9") (pinfunction "AD0_9") (pintype "bidirectional"))
    )
    (net (code "13") (name "ANT_DRV1") (class "Default")
      (node (ref "J6") (pin "P$9") (pinfunction "P$9_P$9") (pintype "bidirectional"))
      (node (ref "UC1") (pin "P$30") (pinfunction "PA13_P$30") (pintype "bidirectional"))
      (node (ref "V6") (pin "P$1") (pinfunction "P$1_P$1") (pintype "bidirectional"))
    )
    (net (code "14") (name "ANT_DRV2") (class "Default")
      (node (ref "J6") (pin "P$8") (pinfunction "P$8_P$8") (pintype "bidirectional"))
      (node (ref "UC1") (pin "P$31") (pinfunction "PA14_P$31") (pintype "bidirectional"))
    )
    (net (code "15") (name "ANT_DRV3") (class "Default")
      (node (ref "J6") (pin "P$7") (pinfunction "P$7_P$7") (pintype "bidirectional"))
      (node (ref "UC1") (pin "P$32") (pinfunction "PA15_P$32") (pintype "bidirectional"))
    )
    (net (code "16") (name "DET_RTN") (class "Default")
      (node (ref "J6") (pin "P$6") (pinfunction "P$6_P$6") (pintype "bidirectional"))
      (node (ref "R56") (pin "2") (pinfunction "2_2") (pintype "passive"))
      (node (ref "UC1") (pin "P$27") (pinfunction "PB14_P$27") (pintype "bidirectional"))
    )
    (net (code "17") (name "GND") (class "Default")
      (node (ref "C1") (pin "2") (pinfunction "P$2_2") (pintype "passive"))
      (node (ref "C10") (pin "2") (pinfunction "P$2_2") (pintype "passive"))
      (node (ref "C11") (pin "2") (pinfunction "P$2_2") (pintype "passive"))
      (node (ref "C12") (pin "2") (pinfunction "P$2_2") (pintype "passive"))
      (node (ref "C13") (pin "2") (pinfunction "P$2_2") (pintype "passive"))
      (node (ref "C14") (pin "2") (pinfunction "P$2_2") (pintype "passive"))
      (node (ref "C15") (pin "2") (pinfunction "P$2_2") (pintype "passive"))
      (node (ref "C16") (pin "2") (pinfunction "P$2_2") (pintype "passive"))
      (node (ref "C18") (pin "2") (pinfunction "P$2_2") (pintype "passive"))
      (node (ref "C19") (pin "2") (pinfunction "P$2_2") (pintype "passive"))
      (node (ref "C2") (pin "2") (pinfunction "P$2_2") (pintype "passive"))
      (node (ref "C20") (pin "2") (pinfunction "P$2_2") (pintype "passive"))
      (node (ref "C21") (pin "2") (pinfunction "P$2_2") (pintype "passive"))
      (node (ref "C22") (pin "2") (pinfunction "P$2_2") (pintype "passive"))
      (node (ref "C23") (pin "2") (pinfunction "P$2_2") (pintype "passive"))
      (node (ref "C24") (pin "2") (pinfunction "P$2_2") (pintype "passive"))
      (node (ref "C25") (pin "2") (pinfunction "P$2_2") (pintype "passive"))
      (node (ref "C26") (pin "2") (pinfunction "P$2_2") (pintype "passive"))
      (node (ref "C27") (pin "2") (pinfunction "P$2_2") (pintype "passive"))
      (node (ref "C29") (pin "2") (pinfunction "P$2_2") (pintype "passive"))
      (node (ref "C3") (pin "2") (pinfunction "P$2_2") (pintype "passive"))
      (node (ref "C30") (pin "1") (pinfunction "P$1_1") (pintype "passive"))
      (node (ref "C31") (pin "1") (pinfunction "P$1_1") (pintype "passive"))
      (node (ref "C32") (pin "2") (pinfunction "P$2_2") (pintype "passive"))
      (node (ref "C33") (pin "2") (pinfunction "P$2_2") (pintype "passive"))
      (node (ref "C34") (pin "2") (pinfunction "P$2_2") (pintype "passive"))
      (node (ref "C4") (pin "2") (pinfunction "P$2_2") (pintype "passive"))
      (node (ref "C5") (pin "2") (pinfunction "P$2_2") (pintype "passive"))
      (node (ref "C6") (pin "2") (pinfunction "P$2_2") (pintype "passive"))
      (node (ref "C7") (pin "2") (pinfunction "P$2_2") (pintype "passive"))
      (node (ref "C8") (pin "2") (pinfunction "P$2_2") (pintype "passive"))
      (node (ref "C9") (pin "2") (pinfunction "P$2_2") (pintype "passive"))
      (node (ref "D10") (pin "C") (pinfunction "C_C") (pintype "passive"))
      (node (ref "D12") (pin "C") (pinfunction "C_C") (pintype "passive"))
      (node (ref "D3") (pin "A") (pinfunction "A_A") (pintype "bidirectional"))
      (node (ref "D4") (pin "A") (pinfunction "A_A") (pintype "bidirectional"))
      (node (ref "D5") (pin "A") (pinfunction "A_A") (pintype "bidirectional"))
      (node (ref "D6") (pin "A") (pinfunction "A_A") (pintype "bidirectional"))
      (node (ref "D7") (pin "C") (pinfunction "C_C") (pintype "passive"))
      (node (ref "D8") (pin "C") (pinfunction "C_C") (pintype "passive"))
      (node (ref "D9") (pin "C") (pinfunction "C_C") (pintype "passive"))
      (node (ref "J1") (pin "P$5") (pinfunction "5_P$5") (pintype "passive"))
      (node (ref "J2") (pin "P$5") (pinfunction "5_P$5") (pintype "passive"))
      (node (ref "J3") (pin "P$5") (pinfunction "P$5_P$5") (pintype "bidirectional"))
      (node (ref "J4") (pin "P$9") (pinfunction "P$9_P$9") (pintype "bidirectional"))
      (node (ref "J5") (pin "P$5") (pinfunction "P$5_P$5") (pintype "bidirectional"))
      (node (ref "J5") (pin "P$6") (pinfunction "P$6_P$6") (pintype "bidirectional"))
      (node (ref "J6") (pin "P$16") (pinfunction "P$16_P$16") (pintype "bidirectional"))
      (node (ref "J6") (pin "P$5") (pinfunction "P$5_P$5") (pintype "bidirectional"))
      (node (ref "J7") (pin "P$5") (pinfunction "P$5_P$5") (pintype "bidirectional"))
      (node (ref "J8") (pin "P$2") (pinfunction "2_P$2") (pintype "bidirectional"))
      (node (ref "J8") (pin "P$9") (pinfunction "9_P$9") (pintype "bidirectional"))
      (node (ref "J9") (pin "P2") (pinfunction "2_P2") (pintype "bidirectional"))
      (node (ref "J9") (pin "P3") (pinfunction "3_P3") (pintype "bidirectional"))
      (node (ref "M1") (pin "P$1") (pinfunction "S_P$1") (pintype "bidirectional"))
      (node (ref "M1") (pin "P$2") (pinfunction "S_P$2") (pintype "bidirectional"))
      (node (ref "M1") (pin "P$3") (pinfunction "S_P$3") (pintype "bidirectional"))
      (node (ref "R11") (pin "1") (pinfunction "1_1") (pintype "passive"))
      (node (ref "R13") (pin "1") (pinfunction "1_1") (pintype "passive"))
      (node (ref "R17") (pin "1") (pinfunction "1_1") (pintype "passive"))
      (node (ref "R19") (pin "1") (pinfunction "1_1") (pintype "passive"))
      (node (ref "R21") (pin "2") (pinfunction "2_2") (pintype "passive"))
      (node (ref "R28") (pin "1") (pinfunction "1_1") (pintype "passive"))
      (node (ref "R29") (pin "1") (pinfunction "1_1") (pintype "passive"))
      (node (ref "R32") (pin "1") (pinfunction "1_1") (pintype "passive"))
      (node (ref "R33") (pin "1") (pinfunction "1_1") (pintype "passive"))
      (node (ref "R35") (pin "1") (pinfunction "1_1") (pintype "passive"))
      (node (ref "R40") (pin "2") (pinfunction "2_2") (pintype "passive"))
      (node (ref "R41") (pin "1") (pinfunction "1_1") (pintype "passive"))
      (node (ref "R43") (pin "1") (pinfunction "1_1") (pintype "passive"))
      (node (ref "R44") (pin "1") (pinfunction "1_1") (pintype "passive"))
      (node (ref "R47") (pin "1") (pinfunction "1_1") (pintype "passive"))
      (node (ref "R49") (pin "1") (pinfunction "1_1") (pintype "passive"))
      (node (ref "R52") (pin "1") (pinfunction "1_1") (pintype "passive"))
      (node (ref "R6") (pin "1") (pinfunction "1_1") (pintype "passive"))
      (node (ref "U1") (pin "P4") (pinfunction "GND_P4") (pintype "bidirectional"))
      (node (ref "U1") (pin "P9") (pinfunction "GND_P9") (pintype "bidirectional"))
      (node (ref "U10") (pin "P$2") (pinfunction "V-_P$2") (pintype "bidirectional"))
      (node (ref "U11") (pin "P$4") (pinfunction "V-_P$4") (pintype "bidirectional"))
      (node (ref "U12") (pin "P$3") (pinfunction "PGND_P$3") (pintype "input"))
      (node (ref "U12") (pin "P$9") (pinfunction "GND_P$9") (pintype "input"))
      (node (ref "U12") (pin "PAD") (pinfunction "GND_PAD") (pintype "input"))
      (node (ref "U13") (pin "P$3") (pinfunction "PGND_P$3") (pintype "input"))
      (node (ref "U13") (pin "P$9") (pinfunction "GND_P$9") (pintype "input"))
      (node (ref "U13") (pin "PAD") (pinfunction "GND_PAD") (pintype "input"))
      (node (ref "U14") (pin "11") (pinfunction "FSYNC_11") (pintype "bidirectional"))
      (node (ref "U14") (pin "18") (pinfunction "GND_18") (pintype "bidirectional"))
      (node (ref "U14") (pin "20") (pinfunction "RESV_20") (pintype "bidirectional"))
      (node (ref "U15") (pin "11") (pinfunction "GND_11") (pintype "bidirectional"))
      (node (ref "U15") (pin "9") (pinfunction "GND_9") (pintype "bidirectional"))
      (node (ref "U2") (pin "P$4") (pinfunction "VSS_P$4") (pintype "bidirectional"))
      (node (ref "U3") (pin "P$3") (pinfunction "GND_P$3") (pintype "bidirectional"))
      (node (ref "U4") (pin "P$3") (pinfunction "GND_P$3") (pintype "bidirectional"))
      (node (ref "U5") (pin "P$1") (pinfunction "GND_P$1") (pintype "bidirectional"))
      (node (ref "U6") (pin "P4") (pinfunction "GND_P4") (pintype "bidirectional"))
      (node (ref "U6") (pin "P9") (pinfunction "GND_P9") (pintype "bidirectional"))
      (node (ref "U7") (pin "P$7") (pinfunction "GND_P$7") (pintype "bidirectional"))
      (node (ref "U8") (pin "P$10") (pinfunction "VEE_P$10") (pintype "bidirectional"))
      (node (ref "U8") (pin "P$11") (pinfunction "GND_P$11") (pintype "bidirectional"))
      (node (ref "U9") (pin "P$10") (pinfunction "VEE_P$10") (pintype "bidirectional"))
      (node (ref "U9") (pin "P$11") (pinfunction "GND_P$11") (pintype "bidirectional"))
      (node (ref "UC1") (pin "P$22") (pinfunction "GND_P$22") (pintype "power_in"))
      (node (ref "UC1") (pin "P$33") (pinfunction "GND_P$33") (pintype "power_in"))
      (node (ref "UC1") (pin "P$47") (pinfunction "GND_P$47") (pintype "power_in"))
      (node (ref "UC1") (pin "P$54") (pinfunction "GND_P$54") (pintype "power_in"))
      (node (ref "UC1") (pin "P$7") (pinfunction "GNDANA_P$7") (pintype "power_in"))
      (node (ref "V10") (pin "P$1") (pinfunction "P$1_P$1") (pintype "bidirectional"))
      (node (ref "V11") (pin "P$1") (pinfunction "P$1_P$1") (pintype "bidirectional"))
      (node (ref "V12") (pin "P$1") (pinfunction "P$1_P$1") (pintype "bidirectional"))
      (node (ref "V9") (pin "P$1") (pinfunction "P$1_P$1") (pintype "bidirectional"))
    )
    (net (code "18") (name "IRVDD") (class "Default")
      (node (ref "J1") (pin "P$4") (pinfunction "4_P$4") (pintype "passive"))
      (node (ref "J2") (pin "P$4") (pinfunction "4_P$4") (pintype "passive"))
      (node (ref "J3") (pin "P$4") (pinfunction "P$4_P$4") (pintype "bidirectional"))
      (node (ref "J4") (pin "P$6") (pinfunction "P$6_P$6") (pintype "bidirectional"))
      (node (ref "J5") (pin "P$2") (pinfunction "P$2_P$2") (pintype "bidirectional"))
      (node (ref "J6") (pin "P$18") (pinfunction "P$18_P$18") (pintype "bidirectional"))
      (node (ref "M2") (pin "5") (pinfunction "D_5") (pintype "passive"))
      (node (ref "M2") (pin "6") (pinfunction "D_6") (pintype "passive"))
      (node (ref "M2") (pin "7") (pinfunction "D_7") (pintype "passive"))
      (node (ref "M2") (pin "8") (pinfunction "D_8") (pintype "passive"))
      (node (ref "R53") (pin "2") (pinfunction "2_2") (pintype "passive"))
    )
    (net (code "19") (name "IR_PWR_CMD") (class "Default")
      (node (ref "M1") (pin "P$4") (pinfunction "G_P$4") (pintype "bidirectional"))
      (node (ref "R21") (pin "1") (pinfunction "1_1") (pintype "passive"))
      (node (ref "UC1") (pin "P$40") (pinfunction "PB17_P$40") (pintype "bidirectional"))
    )
    (net (code "20") (name "L1_DISG") (class "Default")
      (node (ref "J7") (pin "P$18") (pinfunction "P$18_P$18") (pintype "bidirectional"))
      (node (ref "UC1") (pin "P$60") (pinfunction "PB31_P$60") (pintype "bidirectional"))
    )
    (net (code "21") (name "L1_REF") (class "Default")
      (node (ref "J7") (pin "P$20") (pinfunction "P$20_P$20") (pintype "bidirectional"))
      (node (ref "UC1") (pin "P$4") (pinfunction "PA03_P$4") (pintype "bidirectional"))
    )
    (net (code "22") (name "L1_RUN_CHG") (class "Default")
      (node (ref "J7") (pin "P$17") (pinfunction "P$17_P$17") (pintype "bidirectional"))
      (node (ref "UC1") (pin "P$2") (pinfunction "PA01_P$2") (pintype "bidirectional"))
    )
    (net (code "23") (name "L1_TEMP") (class "Default")
      (node (ref "J7") (pin "P$1") (pinfunction "P$1_P$1") (pintype "bidirectional"))
      (node (ref "U8") (pin "P$4") (pinfunction "S3_P$4") (pintype "bidirectional"))
    )
    (net (code "24") (name "L2_DISG") (class "Default")
      (node (ref "J7") (pin "P$19") (pinfunction "P$19_P$19") (pintype "bidirectional"))
      (node (ref "UC1") (pin "P$1") (pinfunction "PA00_P$1") (pintype "bidirectional"))
    )
    (net (code "25") (name "L2_REF") (class "Default")
      (node (ref "J7") (pin "P$8") (pinfunction "P$8_P$8") (pintype "bidirectional"))
      (node (ref "UC1") (pin "P$16") (pinfunction "PA07_P$16") (pintype "bidirectional"))
    )
    (net (code "26") (name "L2_RUN_CHG") (class "Default")
      (node (ref "J7") (pin "P$16") (pinfunction "P$16_P$16") (pintype "bidirectional"))
      (node (ref "UC1") (pin "P$5") (pinfunction "PB04_P$5") (pintype "bidirectional"))
    )
    (net (code "27") (name "L2_TEMP") (class "Default")
      (node (ref "J7") (pin "P$2") (pinfunction "P$2_P$2") (pintype "bidirectional"))
      (node (ref "U8") (pin "P$3") (pinfunction "S2_P$3") (pintype "bidirectional"))
    )
    (net (code "28") (name "LED1SNS") (class "Default")
      (node (ref "J6") (pin "P$15") (pinfunction "P$15_P$15") (pintype "bidirectional"))
      (node (ref "UC1") (pin "P$64") (pinfunction "PB03_P$64") (pintype "bidirectional"))
    )
    (net (code "29") (name "LED1TEMP") (class "Default")
      (node (ref "J6") (pin "P$1") (pinfunction "P$1_P$1") (pintype "bidirectional"))
      (node (ref "U8") (pin "P$8") (pinfunction "S7_P$8") (pintype "bidirectional"))
    )
    (net (code "30") (name "LED2SNS") (class "Default")
      (node (ref "J6") (pin "P$14") (pinfunction "P$14_P$14") (pintype "bidirectional"))
      (node (ref "UC1") (pin "P$63") (pinfunction "PB02_P$63") (pintype "bidirectional"))
    )
    (net (code "31") (name "LED2TEMP") (class "Default")
      (node (ref "J6") (pin "P$2") (pinfunction "P$2_P$2") (pintype "bidirectional"))
      (node (ref "U8") (pin "P$7") (pinfunction "S6_P$7") (pintype "bidirectional"))
    )
    (net (code "32") (name "LED3SNS") (class "Default")
      (node (ref "J6") (pin "P$13") (pinfunction "P$13_P$13") (pintype "bidirectional"))
      (node (ref "UC1") (pin "P$62") (pinfunction "PB01_P$62") (pintype "bidirectional"))
    )
    (net (code "33") (name "LED3TEMP") (class "Default")
      (node (ref "J6") (pin "P$3") (pinfunction "P$3_P$3") (pintype "bidirectional"))
      (node (ref "U8") (pin "P$6") (pinfunction "S5_P$6") (pintype "bidirectional"))
    )
    (net (code "34") (name "LED4SNS") (class "Default")
      (node (ref "J6") (pin "P$12") (pinfunction "P$12_P$12") (pintype "bidirectional"))
      (node (ref "UC1") (pin "P$61") (pinfunction "PB00_P$61") (pintype "bidirectional"))
    )
    (net (code "35") (name "LED4TEMP") (class "Default")
      (node (ref "J6") (pin "P$4") (pinfunction "P$4_P$4") (pintype "bidirectional"))
      (node (ref "U8") (pin "P$5") (pinfunction "S4_P$5") (pintype "bidirectional"))
    )
    (net (code "36") (name "LED_SHDN") (class "Default")
      (node (ref "J6") (pin "P$11") (pinfunction "P$11_P$11") (pintype "bidirectional"))
      (node (ref "R58") (pin "1") (pinfunction "1_1") (pintype "passive"))
      (node (ref "U5") (pin "P$3") (pinfunction "OUT_P$3") (pintype "bidirectional"))
    )
    (net (code "37") (name "LF1REF") (class "Default")
      (node (ref "J7") (pin "P$25") (pinfunction "P$25_P$25") (pintype "bidirectional"))
      (node (ref "UC1") (pin "P$15") (pinfunction "PA06_P$15") (pintype "bidirectional"))
    )
    (net (code "38") (name "LF1_TEMP") (class "Default")
      (node (ref "J7") (pin "P$3") (pinfunction "P$3_P$3") (pintype "bidirectional"))
      (node (ref "U8") (pin "P$2") (pinfunction "S1_P$2") (pintype "bidirectional"))
    )
    (net (code "39") (name "LF2REF") (class "Default")
      (node (ref "J7") (pin "P$12") (pinfunction "P$12_P$12") (pintype "bidirectional"))
      (node (ref "UC1") (pin "P$14") (pinfunction "PA05_P$14") (pintype "bidirectional"))
    )
    (net (code "40") (name "LF3REF") (class "Default")
      (node (ref "J7") (pin "P$13") (pinfunction "P$13_P$13") (pintype "bidirectional"))
      (node (ref "UC1") (pin "P$12") (pinfunction "PB09_P$12") (pintype "bidirectional"))
    )
    (net (code "41") (name "LF3_TEMP") (class "Default")
      (node (ref "J7") (pin "P$4") (pinfunction "P$4_P$4") (pintype "bidirectional"))
      (node (ref "U8") (pin "P$1") (pinfunction "S0_P$1") (pintype "bidirectional"))
    )
    (net (code "42") (name "LF4REF") (class "Default")
      (node (ref "J7") (pin "P$24") (pinfunction "P$24_P$24") (pintype "bidirectional"))
      (node (ref "UC1") (pin "P$13") (pinfunction "PA04_P$13") (pintype "bidirectional"))
    )
    (net (code "43") (name "LFB1OSNS") (class "Default")
      (node (ref "J7") (pin "P$9") (pinfunction "P$9_P$9") (pintype "bidirectional"))
      (node (ref "UC1") (pin "P$20") (pinfunction "PA11_P$20") (pintype "bidirectional"))
    )
    (net (code "44") (name "LFB1SNS") (class "Default")
      (node (ref "J7") (pin "P$10") (pinfunction "P$10_P$10") (pintype "bidirectional"))
      (node (ref "UC1") (pin "P$19") (pinfunction "PA10_P$19") (pintype "bidirectional"))
    )
    (net (code "45") (name "LFB2OSNS") (class "Default")
      (node (ref "J7") (pin "P$27") (pinfunction "P$27_P$27") (pintype "bidirectional"))
      (node (ref "UC1") (pin "P$18") (pinfunction "PA09_P$18") (pintype "bidirectional"))
    )
    (net (code "46") (name "LFB2SNS") (class "Default")
      (node (ref "J7") (pin "P$26") (pinfunction "P$26_P$26") (pintype "bidirectional"))
      (node (ref "UC1") (pin "P$17") (pinfunction "PA08_P$17") (pintype "bidirectional"))
    )
    (net (code "47") (name "LF_B1_OUTEN") (class "Default")
      (node (ref "J7") (pin "P$15") (pinfunction "P$15_P$15") (pintype "bidirectional"))
      (node (ref "UC1") (pin "P$9") (pinfunction "PB06_P$9") (pintype "bidirectional"))
    )
    (net (code "48") (name "LF_B1_RUNCHG") (class "Default")
      (node (ref "J7") (pin "P$21") (pinfunction "P$21_P$21") (pintype "bidirectional"))
      (node (ref "UC1") (pin "P$6") (pinfunction "PB05_P$6") (pintype "bidirectional"))
    )
    (net (code "49") (name "LF_B2_OUTEN") (class "Default")
      (node (ref "J7") (pin "P$14") (pinfunction "P$14_P$14") (pintype "bidirectional"))
      (node (ref "UC1") (pin "P$10") (pinfunction "PB07_P$10") (pintype "bidirectional"))
    )
    (net (code "50") (name "LF_B2_RUNCHG") (class "Default")
      (node (ref "J7") (pin "P$11") (pinfunction "P$11_P$11") (pintype "bidirectional"))
      (node (ref "UC1") (pin "P$23") (pinfunction "PB10_P$23") (pintype "bidirectional"))
    )
    (net (code "51") (name "Net-(C1-P$1)") (class "Default")
      (node (ref "C1") (pin "1") (pinfunction "P$1_1") (pintype "passive"))
      (node (ref "UC1") (pin "P$55") (pinfunction "VDDCORE_P$55") (pintype "power_in"))
    )
    (net (code "52") (name "Net-(C6-P$1)") (class "Default")
      (node (ref "C6") (pin "1") (pinfunction "P$1_1") (pintype "passive"))
      (node (ref "C8") (pin "1") (pinfunction "P$1_1") (pintype "passive"))
      (node (ref "L1") (pin "2") (pinfunction "P$2_2") (pintype "passive"))
      (node (ref "UC1") (pin "P$8") (pinfunction "VDDANA_P$8") (pintype "power_in"))
    )
    (net (code "53") (name "Net-(C14-P$1)") (class "Default")
      (node (ref "C14") (pin "1") (pinfunction "P$1_1") (pintype "passive"))
      (node (ref "R9") (pin "1") (pinfunction "1_1") (pintype "passive"))
      (node (ref "U12") (pin "P$6") (pinfunction "EN_P$6") (pintype "input"))
      (node (ref "U12") (pin "P$7") (pinfunction "PS/SYNC_P$7") (pintype "input"))
      (node (ref "U12") (pin "P$8") (pinfunction "VINA_P$8") (pintype "input"))
    )
    (net (code "54") (name "Net-(C15-P$1)") (class "Default")
      (node (ref "C15") (pin "1") (pinfunction "P$1_1") (pintype "passive"))
      (node (ref "R10") (pin "1") (pinfunction "1_1") (pintype "passive"))
      (node (ref "U13") (pin "P$7") (pinfunction "PS/SYNC_P$7") (pintype "input"))
      (node (ref "U13") (pin "P$8") (pinfunction "VINA_P$8") (pintype "input"))
    )
    (net (code "55") (name "Net-(C16-P$1)") (class "Default")
      (node (ref "C16") (pin "1") (pinfunction "P$1_1") (pintype "passive"))
      (node (ref "U15") (pin "10") (pinfunction "C1_10") (pintype "bidirectional"))
    )
    (net (code "56") (name "Net-(C17-P$1)") (class "Default")
      (node (ref "C17") (pin "1") (pinfunction "P$1_1") (pintype "passive"))
      (node (ref "U15") (pin "8") (pinfunction "SETP_8") (pintype "bidirectional"))
    )
    (net (code "57") (name "Net-(C17-P$2)") (class "Default")
      (node (ref "C17") (pin "2") (pinfunction "P$2_2") (pintype "passive"))
      (node (ref "U15") (pin "12") (pinfunction "SETC_12") (pintype "bidirectional"))
    )
    (net (code "58") (name "Net-(C20-P$1)") (class "Default")
      (node (ref "C20") (pin "1") (pinfunction "P$1_1") (pintype "passive"))
      (node (ref "U14") (pin "10") (pinfunction "REGOUT_10") (pintype "bidirectional"))
    )
    (net (code "59") (name "Net-(C26-P$1)") (class "Default")
      (node (ref "C26") (pin "1") (pinfunction "P$1_1") (pintype "passive"))
      (node (ref "R23") (pin "2") (pinfunction "2_2") (pintype "passive"))
      (node (ref "U5") (pin "P$6") (pinfunction "THRSH_P$6") (pintype "bidirectional"))
      (node (ref "U5") (pin "P$7") (pinfunction "DISG_P$7") (pintype "bidirectional"))
    )
    (net (code "60") (name "Net-(C27-P$1)") (class "Default")
      (node (ref "C27") (pin "1") (pinfunction "P$1_1") (pintype "passive"))
      (node (ref "U5") (pin "P$5") (pinfunction "CV_P$5") (pintype "bidirectional"))
    )
    (net (code "61") (name "Net-(D7-PadA)") (class "Default")
      (node (ref "D7") (pin "A") (pinfunction "A_A") (pintype "passive"))
      (node (ref "R53") (pin "1") (pinfunction "1_1") (pintype "passive"))
    )
    (net (code "62") (name "Net-(D8-PadA)") (class "Default")
      (node (ref "D8") (pin "A") (pinfunction "A_A") (pintype "passive"))
      (node (ref "R54") (pin "1") (pinfunction "1_1") (pintype "passive"))
    )
    (net (code "63") (name "Net-(D9-PadA)") (class "Default")
      (node (ref "D9") (pin "A") (pinfunction "A_A") (pintype "passive"))
      (node (ref "R55") (pin "1") (pinfunction "1_1") (pintype "passive"))
    )
    (net (code "64") (name "Net-(D10-PadA)") (class "Default")
      (node (ref "D10") (pin "A") (pinfunction "A_A") (pintype "passive"))
      (node (ref "R56") (pin "1") (pinfunction "1_1") (pintype "passive"))
    )
    (net (code "65") (name "Net-(D12-PadA)") (class "Default")
      (node (ref "D12") (pin "A") (pinfunction "A_A") (pintype "passive"))
      (node (ref "R58") (pin "2") (pinfunction "2_2") (pintype "passive"))
    )
    (net (code "66") (name "Net-(M2-G)") (class "Default")
      (node (ref "M1") (pin "P$5") (pinfunction "D_P$5") (pintype "bidirectional"))
      (node (ref "M1") (pin "P$6") (pinfunction "D_P$6") (pintype "bidirectional"))
      (node (ref "M1") (pin "P$7") (pinfunction "D_P$7") (pintype "bidirectional"))
      (node (ref "M1") (pin "P$8") (pinfunction "D_P$8") (pintype "bidirectional"))
      (node (ref "M1") (pin "PAD") (pinfunction "D_PAD") (pintype "bidirectional"))
      (node (ref "M2") (pin "4") (pinfunction "G_4") (pintype "passive"))
      (node (ref "R22") (pin "1") (pinfunction "1_1") (pintype "passive"))
    )
    (net (code "67") (name "Net-(R38-Pad2)") (class "Default")
      (node (ref "R38") (pin "2") (pinfunction "2_2") (pintype "passive"))
      (node (ref "R39") (pin "2") (pinfunction "2_2") (pintype "passive"))
      (node (ref "R40") (pin "1") (pinfunction "1_1") (pintype "passive"))
    )
    (net (code "68") (name "Net-(U1-~{HOLD})") (class "Default")
      (node (ref "R1") (pin "1") (pinfunction "1_1") (pintype "passive"))
      (node (ref "U1") (pin "P7") (pinfunction "~{HOLD}_P7") (pintype "bidirectional"))
    )
    (net (code "69") (name "Net-(U1-~{WP})") (class "Default")
      (node (ref "R3") (pin "1") (pinfunction "1_1") (pintype "passive"))
      (node (ref "U1") (pin "P3") (pinfunction "~{WP}_P3") (pintype "bidirectional"))
    )
    (net (code "70") (name "Net-(U2-E2)") (class "Default")
      (node (ref "R17") (pin "2") (pinfunction "2_2") (pintype "passive"))
      (node (ref "R18") (pin "1") (pinfunction "1_1") (pintype "passive"))
      (node (ref "U2") (pin "P$3") (pinfunction "E2_P$3") (pintype "bidirectional"))
    )
    (net (code "71") (name "Net-(U2-~{WC})") (class "Default")
      (node (ref "R19") (pin "2") (pinfunction "2_2") (pintype "passive"))
      (node (ref "U2") (pin "P$7") (pinfunction "~{WC}_P$7") (pintype "bidirectional"))
    )
    (net (code "72") (name "Net-(U6-~{HOLD})") (class "Default")
      (node (ref "R14") (pin "1") (pinfunction "1_1") (pintype "passive"))
      (node (ref "U6") (pin "P7") (pinfunction "~{HOLD}_P7") (pintype "bidirectional"))
    )
    (net (code "73") (name "Net-(U6-~{WP})") (class "Default")
      (node (ref "R16") (pin "1") (pinfunction "1_1") (pintype "passive"))
      (node (ref "U6") (pin "P3") (pinfunction "~{WP}_P3") (pintype "bidirectional"))
    )
    (net (code "74") (name "Net-(U10-+)") (class "Default")
      (node (ref "R34") (pin "2") (pinfunction "2_2") (pintype "passive"))
      (node (ref "R35") (pin "2") (pinfunction "2_2") (pintype "passive"))
      (node (ref "U10") (pin "P$3") (pinfunction "+_P$3") (pintype "bidirectional"))
    )
    (net (code "75") (name "Net-(U10--)") (class "Default")
      (node (ref "R37") (pin "2") (pinfunction "2_2") (pintype "passive"))
      (node (ref "R38") (pin "1") (pinfunction "1_1") (pintype "passive"))
      (node (ref "U10") (pin "P$4") (pinfunction "-_P$4") (pintype "bidirectional"))
    )
    (net (code "76") (name "Net-(U10-OUT)") (class "Default")
      (node (ref "R36") (pin "2") (pinfunction "2_2") (pintype "passive"))
      (node (ref "R37") (pin "1") (pinfunction "1_1") (pintype "passive"))
      (node (ref "U10") (pin "P$1") (pinfunction "OUT_P$1") (pintype "bidirectional"))
    )
    (net (code "77") (name "Net-(U11-A+)") (class "Default")
      (node (ref "R42") (pin "1") (pinfunction "1_1") (pintype "passive"))
      (node (ref "R43") (pin "2") (pinfunction "2_2") (pintype "passive"))
      (node (ref "U11") (pin "P$3") (pinfunction "A+_P$3") (pintype "bidirectional"))
    )
    (net (code "78") (name "Net-(U11-B+)") (class "Default")
      (node (ref "D2") (pin "A") (pinfunction "A_A") (pintype "bidirectional"))
      (node (ref "U11") (pin "P$1") (pinfunction "OUTA_P$1") (pintype "bidirectional"))
      (node (ref "U11") (pin "P$5") (pinfunction "B+_P$5") (pintype "bidirectional"))
    )
    (net (code "79") (name "Net-(U11-B-)") (class "Default")
      (node (ref "R44") (pin "2") (pinfunction "2_2") (pintype "passive"))
      (node (ref "R45") (pin "2") (pinfunction "2_2") (pintype "passive"))
      (node (ref "U11") (pin "P$6") (pinfunction "B-_P$6") (pintype "bidirectional"))
    )
    (net (code "80") (name "Net-(U12-L1)") (class "Default")
      (node (ref "L2") (pin "1") (pinfunction "1_1") (pintype "passive"))
      (node (ref "U12") (pin "P$4") (pinfunction "L1_P$4") (pintype "input"))
    )
    (net (code "81") (name "Net-(U12-L2)") (class "Default")
      (node (ref "L2") (pin "2") (pinfunction "2_2") (pintype "passive"))
      (node (ref "U12") (pin "P$2") (pinfunction "L2_P$2") (pintype "input"))
    )
    (net (code "82") (name "Net-(U13-L1)") (class "Default")
      (node (ref "L3") (pin "1") (pinfunction "1_1") (pintype "passive"))
      (node (ref "U13") (pin "P$4") (pinfunction "L1_P$4") (pintype "input"))
    )
    (net (code "83") (name "Net-(U13-L2)") (class "Default")
      (node (ref "L3") (pin "2") (pinfunction "2_2") (pintype "passive"))
      (node (ref "U13") (pin "P$2") (pinfunction "L2_P$2") (pintype "input"))
    )
    (net (code "84") (name "PD_FLASH") (class "Default")
      (node (ref "J6") (pin "P$10") (pinfunction "P$10_P$10") (pintype "bidirectional"))
      (node (ref "U9") (pin "P$4") (pinfunction "S3_P$4") (pintype "bidirectional"))
    )
    (net (code "85") (name "PD_IN") (class "Default")
      (node (ref "D2") (pin "C") (pinfunction "C_C") (pintype "bidirectional"))
      (node (ref "U11") (pin "P$2") (pinfunction "A-_P$2") (pintype "bidirectional"))
      (node (ref "U9") (pin "P$9") (pinfunction "DO_P$9") (pintype "bidirectional"))
    )
    (net (code "86") (name "PD_OUT") (class "Default")
      (node (ref "R45") (pin "1") (pinfunction "1_1") (pintype "passive"))
      (node (ref "U11") (pin "P$7") (pinfunction "OUTB_P$7") (pintype "bidirectional"))
      (node (ref "UC1") (pin "P$3") (pinfunction "PA02_P$3") (pintype "bidirectional"))
    )
    (net (code "87") (name "PD_XN") (class "Default")
      (node (ref "J2") (pin "P$1") (pinfunction "1_P$1") (pintype "passive"))
      (node (ref "U9") (pin "P$2") (pinfunction "S1_P$2") (pintype "bidirectional"))
    )
    (net (code "88") (name "PD_XP") (class "Default")
      (node (ref "J5") (pin "P$1") (pinfunction "P$1_P$1") (pintype "bidirectional"))
      (node (ref "U9") (pin "P$6") (pinfunction "S5_P$6") (pintype "bidirectional"))
    )
    (net (code "89") (name "PD_YN") (class "Default")
      (node (ref "J1") (pin "P$1") (pinfunction "1_P$1") (pintype "passive"))
      (node (ref "U9") (pin "P$3") (pinfunction "S2_P$3") (pintype "bidirectional"))
    )
    (net (code "90") (name "PD_ZN") (class "Default")
      (node (ref "J4") (pin "P$5") (pinfunction "P$5_P$5") (pintype "bidirectional"))
      (node (ref "U9") (pin "P$5") (pinfunction "S4_P$5") (pintype "bidirectional"))
    )
    (net (code "91") (name "PD_ZP") (class "Default")
      (node (ref "J3") (pin "P$1") (pinfunction "P$1_P$1") (pintype "bidirectional"))
      (node (ref "U9") (pin "P$1") (pinfunction "S0_P$1") (pintype "bidirectional"))
    )
    (net (code "92") (name "RAD_PWR_RUN") (class "Default")
      (node (ref "J8") (pin "P$7") (pinfunction "7_P$7") (pintype "bidirectional"))
      (node (ref "UC1") (pin "P$41") (pinfunction "PA20_P$41") (pintype "bidirectional"))
    )
    (net (code "93") (name "RX_DATA") (class "Default")
      (node (ref "R20") (pin "1") (pinfunction "1_1") (pintype "passive"))
      (node (ref "U3") (pin "P$4") (pinfunction "Y_P$4") (pintype "bidirectional"))
      (node (ref "UC1") (pin "P$46") (pinfunction "PA25_P$46") (pintype "bidirectional"))
      (node (ref "V1") (pin "P$1") (pinfunction "P$1_P$1") (pintype "bidirectional"))
    )
    (net (code "94") (name "RX_EN") (class "Default")
      (node (ref "U3") (pin "P$1") (pinfunction "~{OE}_P$1") (pintype "bidirectional"))
      (node (ref "UC1") (pin "P$43") (pinfunction "PA22_P$43") (pintype "bidirectional"))
    )
    (net (code "95") (name "RX_IN") (class "Default")
      (node (ref "J8") (pin "P$4") (pinfunction "4_P$4") (pintype "bidirectional"))
      (node (ref "R20") (pin "2") (pinfunction "2_2") (pintype "passive"))
      (node (ref "U3") (pin "P$2") (pinfunction "A_P$2") (pintype "bidirectional"))
    )
    (net (code "96") (name "SCK") (class "Default")
      (node (ref "R6") (pin "2") (pinfunction "2_2") (pintype "passive"))
      (node (ref "U1") (pin "P6") (pinfunction "SCK_P6") (pintype "bidirectional"))
      (node (ref "U6") (pin "P6") (pinfunction "SCK_P6") (pintype "bidirectional"))
      (node (ref "UC1") (pin "P$38") (pinfunction "PA19_P$38") (pintype "bidirectional"))
    )
    (net (code "97") (name "SCL") (class "Default")
      (node (ref "J1") (pin "P$2") (pinfunction "2_P$2") (pintype "passive"))
      (node (ref "J2") (pin "P$2") (pinfunction "2_P$2") (pintype "passive"))
      (node (ref "J3") (pin "P$3") (pinfunction "P$3_P$3") (pintype "bidirectional"))
      (node (ref "J4") (pin "P$4") (pinfunction "P$4_P$4") (pintype "bidirectional"))
      (node (ref "J5") (pin "P$4") (pinfunction "P$4_P$4") (pintype "bidirectional"))
      (node (ref "J6") (pin "P$20") (pinfunction "P$20_P$20") (pintype "bidirectional"))
      (node (ref "J7") (pin "P$23") (pinfunction "P$23_P$23") (pintype "bidirectional"))
      (node (ref "R7") (pin "1") (pinfunction "1_1") (pintype "passive"))
      (node (ref "U14") (pin "23") (pinfunction "SCL_23") (pintype "bidirectional"))
      (node (ref "U15") (pin "1") (pinfunction "SCL_1") (pintype "bidirectional"))
      (node (ref "U2") (pin "P$6") (pinfunction "SCL_P$6") (pintype "bidirectional"))
      (node (ref "U7") (pin "P$1") (pinfunction "SCL_P$1") (pintype "bidirectional"))
      (node (ref "U8") (pin "P$15") (pinfunction "SCL_P$15") (pintype "bidirectional"))
      (node (ref "U9") (pin "P$15") (pinfunction "SCL_P$15") (pintype "bidirectional"))
      (node (ref "UC1") (pin "P$26") (pinfunction "PB13_P$26") (pintype "bidirectional"))
      (node (ref "V5") (pin "P$1") (pinfunction "P$1_P$1") (pintype "bidirectional"))
    )
    (net (code "98") (name "SDA") (class "Default")
      (node (ref "J1") (pin "P$3") (pinfunction "3_P$3") (pintype "passive"))
      (node (ref "J2") (pin "P$3") (pinfunction "3_P$3") (pintype "passive"))
      (node (ref "J3") (pin "P$2") (pinfunction "P$2_P$2") (pintype "bidirectional"))
      (node (ref "J4") (pin "P$3") (pinfunction "P$3_P$3") (pintype "bidirectional"))
      (node (ref "J5") (pin "P$3") (pinfunction "P$3_P$3") (pintype "bidirectional"))
      (node (ref "J6") (pin "P$19") (pinfunction "P$19_P$19") (pintype "bidirectional"))
      (node (ref "J7") (pin "P$22") (pinfunction "P$22_P$22") (pintype "bidirectional"))
      (node (ref "R8") (pin "1") (pinfunction "1_1") (pintype "passive"))
      (node (ref "U14") (pin "24") (pinfunction "SDA_24") (pintype "bidirectional"))
      (node (ref "U15") (pin "16") (pinfunction "SDA_16") (pintype "bidirectional"))
      (node (ref "U2") (pin "P$5") (pinfunction "SDA_P$5") (pintype "bidirectional"))
      (node (ref "U7") (pin "P$2") (pinfunction "SDA_P$2") (pintype "bidirectional"))
      (node (ref "U8") (pin "P$14") (pinfunction "SDA_P$14") (pintype "bidirectional"))
      (node (ref "U9") (pin "P$14") (pinfunction "SDA_P$14") (pintype "bidirectional"))
      (node (ref "UC1") (pin "P$25") (pinfunction "PB12_P$25") (pintype "bidirectional"))
      (node (ref "V4") (pin "P$1") (pinfunction "P$1_P$1") (pintype "bidirectional"))
    )
    (net (code "99") (name "SI") (class "Default")
      (node (ref "R5") (pin "1") (pinfunction "1_1") (pintype "passive"))
      (node (ref "U1") (pin "P5") (pinfunction "SI_P5") (pintype "bidirectional"))
      (node (ref "U6") (pin "P5") (pinfunction "SI_P5") (pintype "bidirectional"))
      (node (ref "UC1") (pin "P$37") (pinfunction "PA18_P$37") (pintype "bidirectional"))
    )
    (net (code "100") (name "SO") (class "Default")
      (node (ref "R4") (pin "1") (pinfunction "1_1") (pintype "passive"))
      (node (ref "U1") (pin "P2") (pinfunction "SO_P2") (pintype "bidirectional"))
      (node (ref "U6") (pin "P2") (pinfunction "SO_P2") (pintype "bidirectional"))
      (node (ref "UC1") (pin "P$35") (pinfunction "PA16_P$35") (pintype "bidirectional"))
    )
    (net (code "101") (name "SWDCLK") (class "Default")
      (node (ref "J4") (pin "P$7") (pinfunction "P$7_P$7") (pintype "bidirectional"))
      (node (ref "J9") (pin "P9") (pinfunction "9_P9") (pintype "bidirectional"))
      (node (ref "UC1") (pin "P$57") (pinfunction "PA30_P$57") (pintype "bidirectional"))
    )
    (net (code "102") (name "SWDIO") (class "Default")
      (node (ref "J4") (pin "P$8") (pinfunction "P$8_P$8") (pintype "bidirectional"))
      (node (ref "J9") (pin "P10") (pinfunction "10_P10") (pintype "bidirectional"))
      (node (ref "UC1") (pin "P$58") (pinfunction "PA31_P$58") (pintype "bidirectional"))
    )
    (net (code "103") (name "TEMP_IN") (class "Default")
      (node (ref "R34") (pin "1") (pinfunction "1_1") (pintype "passive"))
      (node (ref "R41") (pin "2") (pinfunction "2_2") (pintype "passive"))
      (node (ref "U8") (pin "P$9") (pinfunction "DO_P$9") (pintype "bidirectional"))
    )
    (net (code "104") (name "TEMP_OUT") (class "Default")
      (node (ref "C32") (pin "1") (pinfunction "P$1_1") (pintype "passive"))
      (node (ref "R36") (pin "1") (pinfunction "1_1") (pintype "passive"))
      (node (ref "UC1") (pin "P$11") (pinfunction "PB08_P$11") (pintype "bidirectional"))
    )
    (net (code "105") (name "TRIG") (class "Default")
      (node (ref "C28") (pin "2") (pinfunction "P$2_2") (pintype "passive"))
      (node (ref "D1") (pin "A") (pinfunction "A_A") (pintype "bidirectional"))
      (node (ref "R24") (pin "2") (pinfunction "2_2") (pintype "passive"))
      (node (ref "U5") (pin "P$2") (pinfunction "TRIG_P$2") (pintype "bidirectional"))
    )
    (net (code "106") (name "TX_DATA") (class "Default")
      (node (ref "U4") (pin "P$2") (pinfunction "A_P$2") (pintype "bidirectional"))
      (node (ref "UC1") (pin "P$45") (pinfunction "PA24_P$45") (pintype "bidirectional"))
      (node (ref "V2") (pin "P$1") (pinfunction "P$1_P$1") (pintype "bidirectional"))
    )
    (net (code "107") (name "TX_EN") (class "Default")
      (node (ref "U4") (pin "P$1") (pinfunction "~{OE}_P$1") (pintype "bidirectional"))
      (node (ref "UC1") (pin "P$44") (pinfunction "PA23_P$44") (pintype "bidirectional"))
    )
    (net (code "108") (name "TX_OUT") (class "Default")
      (node (ref "J8") (pin "P$6") (pinfunction "6_P$6") (pintype "bidirectional"))
      (node (ref "U4") (pin "P$4") (pinfunction "Y_P$4") (pintype "bidirectional"))
    )
    (net (code "109") (name "VIN") (class "Default")
      (node (ref "C10") (pin "1") (pinfunction "P$1_1") (pintype "passive"))
      (node (ref "C11") (pin "1") (pinfunction "P$1_1") (pintype "passive"))
      (node (ref "J8") (pin "P$1") (pinfunction "1_P$1") (pintype "bidirectional"))
      (node (ref "J8") (pin "P$10") (pinfunction "10_P$10") (pintype "bidirectional"))
      (node (ref "R10") (pin "2") (pinfunction "2_2") (pintype "passive"))
      (node (ref "R50") (pin "P$1") (pinfunction "1_P$1") (pintype "passive"))
      (node (ref "R51") (pin "P$2") (pinfunction "2_P$2") (pintype "passive"))
      (node (ref "R52") (pin "2") (pinfunction "2_2") (pintype "passive"))
      (node (ref "R9") (pin "2") (pinfunction "2_2") (pintype "passive"))
      (node (ref "U12") (pin "P$5") (pinfunction "VIN_P$5") (pintype "input"))
      (node (ref "U13") (pin "P$5") (pinfunction "VIN_P$5") (pintype "input"))
      (node (ref "V3") (pin "P$1") (pinfunction "P$1_P$1") (pintype "bidirectional"))
    )
    (net (code "110") (name "VIN-EXT") (class "Default")
      (node (ref "D4") (pin "C") (pinfunction "C_C") (pintype "bidirectional"))
      (node (ref "J4") (pin "P$1") (pinfunction "P$1_P$1") (pintype "bidirectional"))
      (node (ref "R51") (pin "P$1") (pinfunction "1_P$1") (pintype "passive"))
    )
    (net (code "111") (name "VIN-INT") (class "Default")
      (node (ref "D3") (pin "C") (pinfunction "C_C") (pintype "bidirectional"))
      (node (ref "J5") (pin "P$7") (pinfunction "P$7_P$7") (pintype "bidirectional"))
      (node (ref "J5") (pin "P$8") (pinfunction "P$8_P$8") (pintype "bidirectional"))
      (node (ref "R50") (pin "P$2") (pinfunction "2_P$2") (pintype "passive"))
    )
    (net (code "112") (name "unconnected-(J1-6-PadP$6)") (class "Default")
      (node (ref "J1") (pin "P$6") (pinfunction "6_P$6") (pintype "passive"))
    )
    (net (code "113") (name "unconnected-(J2-6-PadP$6)") (class "Default")
      (node (ref "J2") (pin "P$6") (pinfunction "6_P$6") (pintype "passive"))
    )
    (net (code "114") (name "unconnected-(J3-PadP$6)") (class "Default")
      (node (ref "J3") (pin "P$6") (pinfunction "P$6_P$6") (pintype "bidirectional"))
    )
    (net (code "115") (name "unconnected-(J9-4-PadP4)") (class "Default")
      (node (ref "J9") (pin "P4") (pinfunction "4_P4") (pintype "bidirectional"))
    )
    (net (code "116") (name "unconnected-(J9-5-PadP5)") (class "Default")
      (node (ref "J9") (pin "P5") (pinfunction "5_P5") (pintype "bidirectional"))
    )
    (net (code "117") (name "unconnected-(J9-7-PadP7)") (class "Default")
      (node (ref "J9") (pin "P7") (pinfunction "7_P7") (pintype "bidirectional"))
    )
    (net (code "118") (name "unconnected-(J9-8-PadP8)") (class "Default")
      (node (ref "J9") (pin "P8") (pinfunction "8_P8") (pintype "bidirectional"))
    )
    (net (code "119") (name "unconnected-(U9-S6-PadP$7)") (class "Default")
      (node (ref "U9") (pin "P$7") (pinfunction "S6_P$7") (pintype "bidirectional"))
    )
    (net (code "120") (name "unconnected-(U9-S7-PadP$8)") (class "Default")
      (node (ref "U9") (pin "P$8") (pinfunction "S7_P$8") (pintype "bidirectional"))
    )
    (net (code "121") (name "unconnected-(U14-AUX_CL-Pad7)") (class "Default")
      (node (ref "U14") (pin "7") (pinfunction "AUX_CL_7") (pintype "bidirectional"))
    )
    (net (code "122") (name "unconnected-(U14-AUX_DA-Pad21)") (class "Default")
      (node (ref "U14") (pin "21") (pinfunction "AUX_DA_21") (pintype "bidirectional"))
    )
    (net (code "123") (name "unconnected-(U14-INT-Pad12)") (class "Default")
      (node (ref "U14") (pin "12") (pinfunction "INT_12") (pintype "bidirectional"))
    )
    (net (code "124") (name "unconnected-(U14-NCS-Pad22)") (class "Default")
      (node (ref "U14") (pin "22") (pinfunction "NCS_22") (pintype "bidirectional"))
    )
    (net (code "125") (name "unconnected-(U14-RESV-Pad19)") (class "Default")
      (node (ref "U14") (pin "19") (pinfunction "RESV_19") (pintype "bidirectional"))
    )
    (net (code "126") (name "unconnected-(U15-DRDY-Pad15)") (class "Default")
      (node (ref "U15") (pin "15") (pinfunction "DRDY_15") (pintype "bidirectional"))
    )
    (net (code "127") (name "unconnected-(U15-NC-Pad3)") (class "Default")
      (node (ref "U15") (pin "3") (pinfunction "NC_3") (pintype "bidirectional"))
    )
    (net (code "128") (name "unconnected-(U15-NC-Pad5)") (class "Default")
      (node (ref "U15") (pin "5") (pinfunction "NC_5") (pintype "bidirectional"))
    )
    (net (code "129") (name "unconnected-(U15-NC-Pad6)") (class "Default")
      (node (ref "U15") (pin "6") (pinfunction "NC_6") (pintype "bidirectional"))
    )
    (net (code "130") (name "unconnected-(U15-NC-Pad7)") (class "Default")
      (node (ref "U15") (pin "7") (pinfunction "NC_7") (pintype "bidirectional"))
    )
    (net (code "131") (name "unconnected-(U15-NC-Pad14)") (class "Default")
      (node (ref "U15") (pin "14") (pinfunction "NC_14") (pintype "bidirectional"))
    )
    (net (code "132") (name "unconnected-(UC1-PA27-PadP$51)") (class "Default")
      (node (ref "UC1") (pin "P$51") (pinfunction "PA27_P$51") (pintype "bidirectional"))
    )
    (net (code "133") (name "unconnected-(UC1-PA28-PadP$53)") (class "Default")
      (node (ref "UC1") (pin "P$53") (pinfunction "PA28_P$53") (pintype "bidirectional"))
    )
    (net (code "134") (name "unconnected-(UC1-PB15-PadP$28)") (class "Default")
      (node (ref "UC1") (pin "P$28") (pinfunction "PB15_P$28") (pintype "bidirectional"))
    )
    (net (code "135") (name "unconnected-(UC1-PB22-PadP$49)") (class "Default")
      (node (ref "UC1") (pin "P$49") (pinfunction "PB22_P$49") (pintype "bidirectional"))
    )
    (net (code "136") (name "unconnected-(UC1-PB23-PadP$50)") (class "Default")
      (node (ref "UC1") (pin "P$50") (pinfunction "PB23_P$50") (pintype "bidirectional"))
    )
    (net (code "137") (name "unconnected-(UC1-PB30-PadP$59)") (class "Default")
      (node (ref "UC1") (pin "P$59") (pinfunction "PB30_P$59") (pintype "bidirectional"))
    )
    (net (code "138") (name "~{CS2}") (class "Default")
      (node (ref "R15") (pin "1") (pinfunction "1_1") (pintype "passive"))
      (node (ref "U6") (pin "P1") (pinfunction "~{CS}_P1") (pintype "bidirectional"))
      (node (ref "UC1") (pin "P$39") (pinfunction "PB16_P$39") (pintype "bidirectional"))
    )
    (net (code "139") (name "~{CS}") (class "Default")
      (node (ref "R2") (pin "1") (pinfunction "1_1") (pintype "passive"))
      (node (ref "U1") (pin "P1") (pinfunction "~{CS}_P1") (pintype "bidirectional"))
      (node (ref "UC1") (pin "P$36") (pinfunction "PA17_P$36") (pintype "bidirectional"))
    )
    (net (code "140") (name "~{LED_CMD}") (class "Default")
      (node (ref "C28") (pin "1") (pinfunction "P$1_1") (pintype "passive"))
      (node (ref "R25") (pin "2") (pinfunction "2_2") (pintype "passive"))
      (node (ref "UC1") (pin "P$29") (pinfunction "PA12_P$29") (pintype "bidirectional"))
    )
    (net (code "141") (name "~{RAD_SHDN}") (class "Default")
      (node (ref "J8") (pin "P$5") (pinfunction "5_P$5") (pintype "bidirectional"))
      (node (ref "UC1") (pin "P$42") (pinfunction "PA21_P$42") (pintype "bidirectional"))
    )
    (net (code "142") (name "~{RESET}") (class "Default")
      (node (ref "J4") (pin "P$2") (pinfunction "P$2_P$2") (pintype "bidirectional"))
      (node (ref "J9") (pin "P6") (pinfunction "6_P6") (pintype "bidirectional"))
      (node (ref "UC1") (pin "P$52") (pinfunction "RESETN_P$52") (pintype "input"))
    )
  )
)
